# BSPD_SDC.net
KiCad netlist of a schematic drawn in Altium Designer
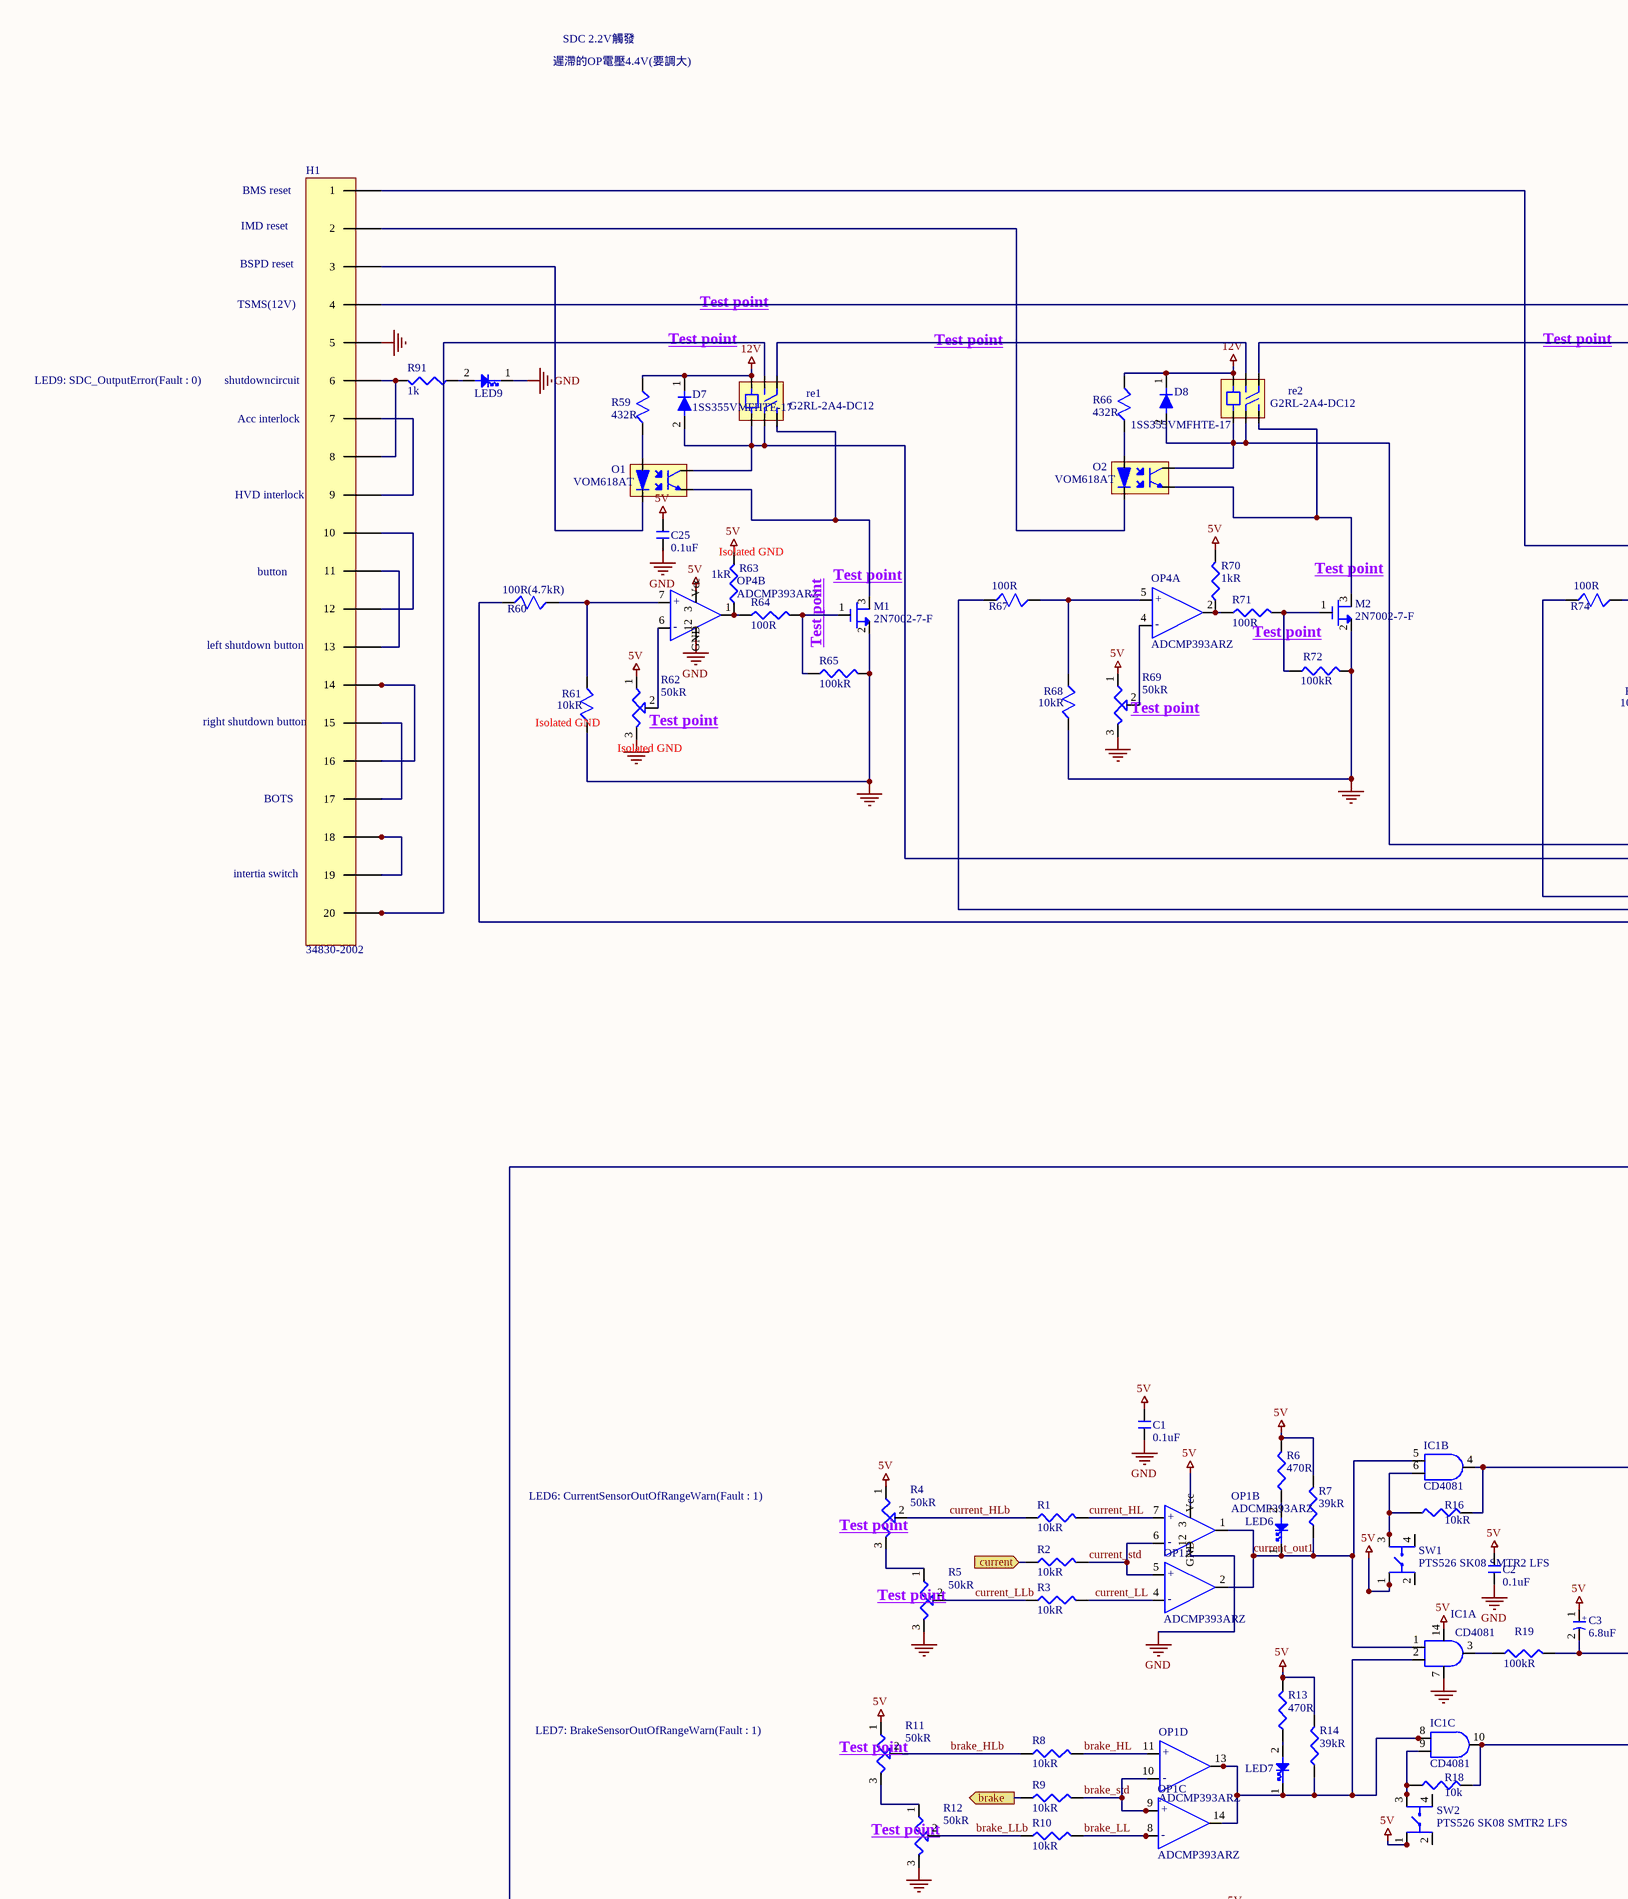
[diagram p0: BSPD+SDC.SchDoc, top left]
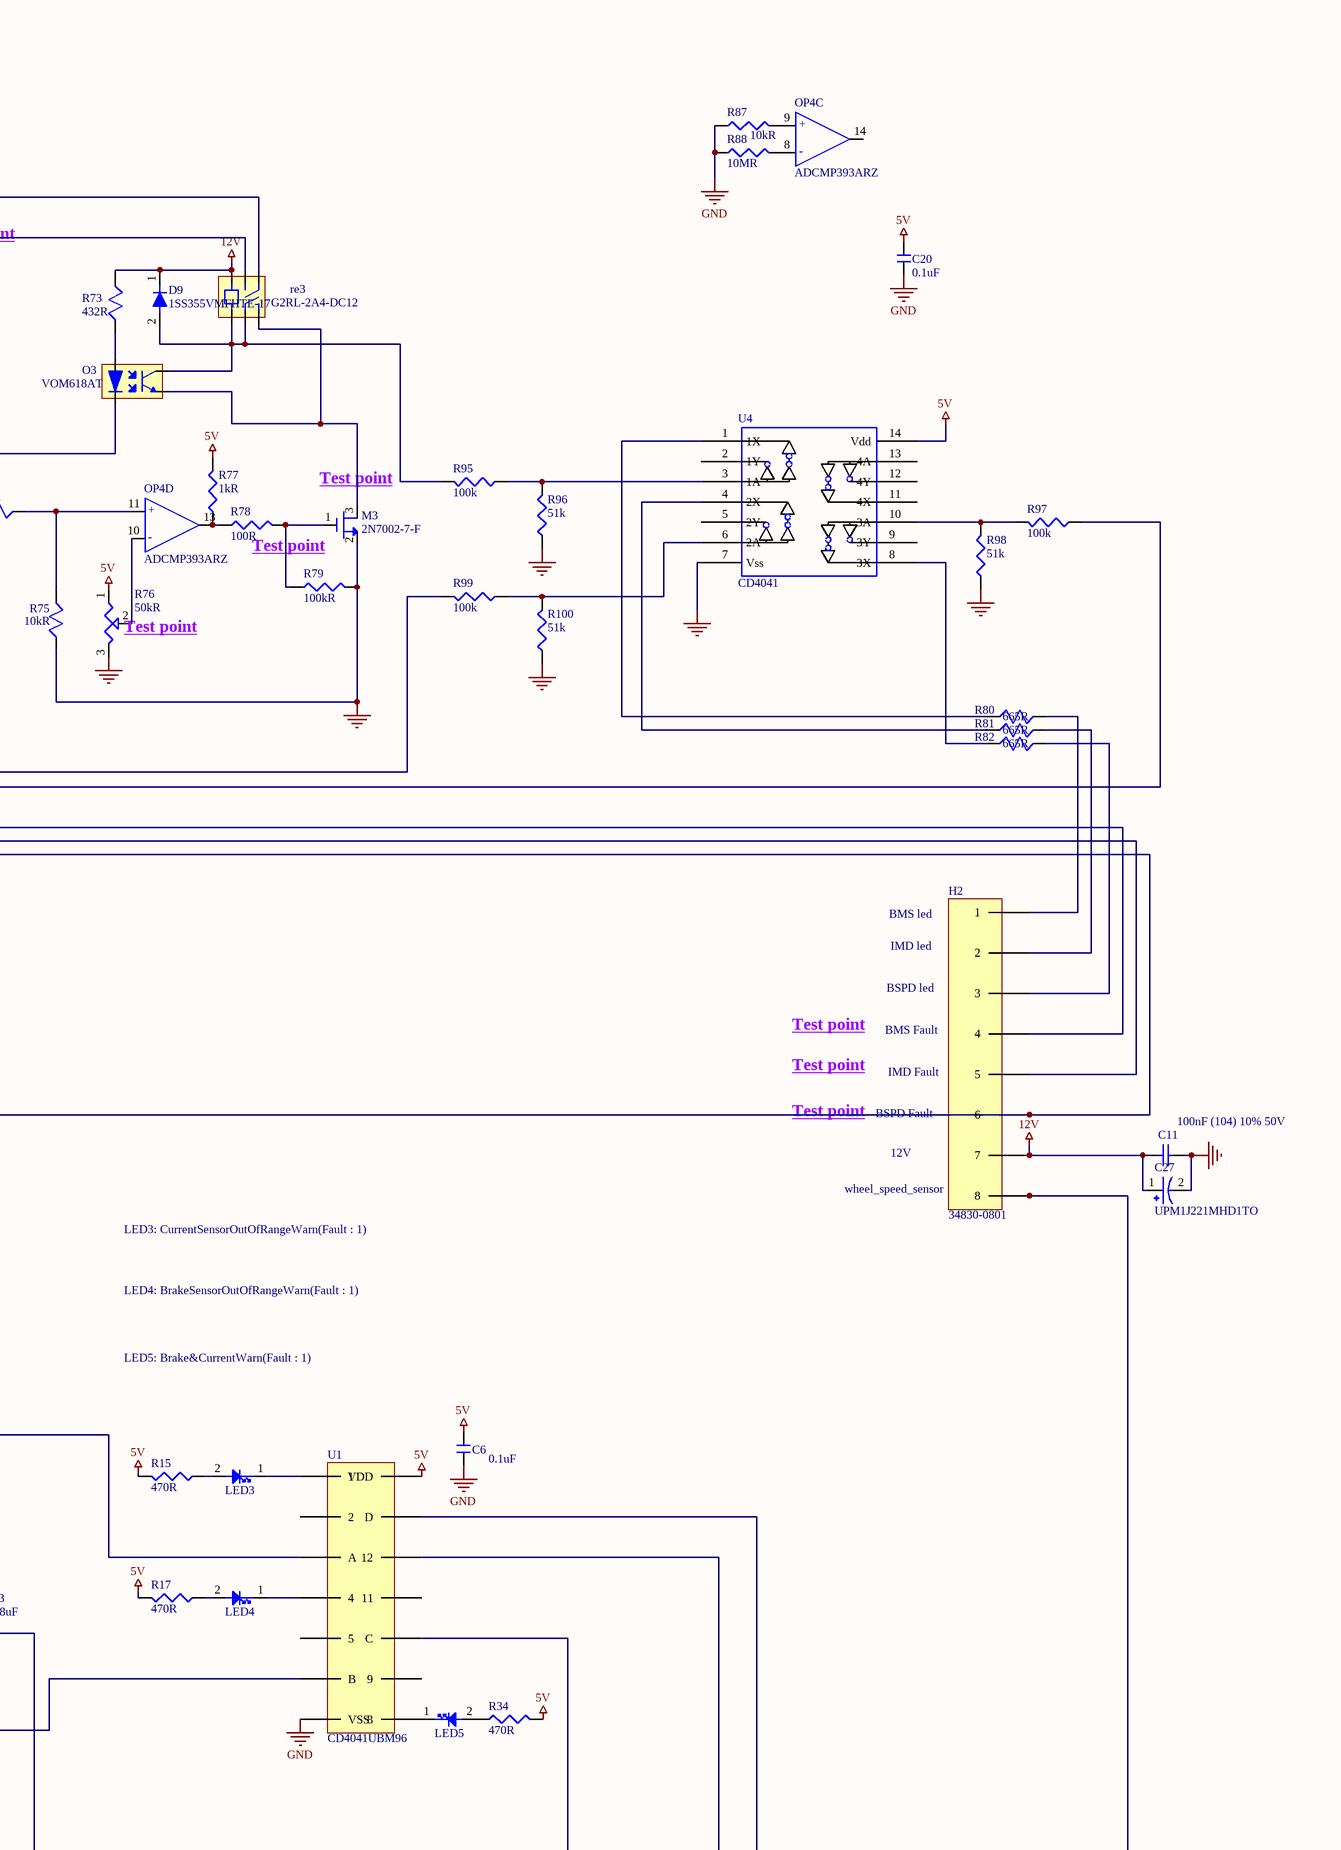
[diagram p1: BSPD+SDC.SchDoc, top right]
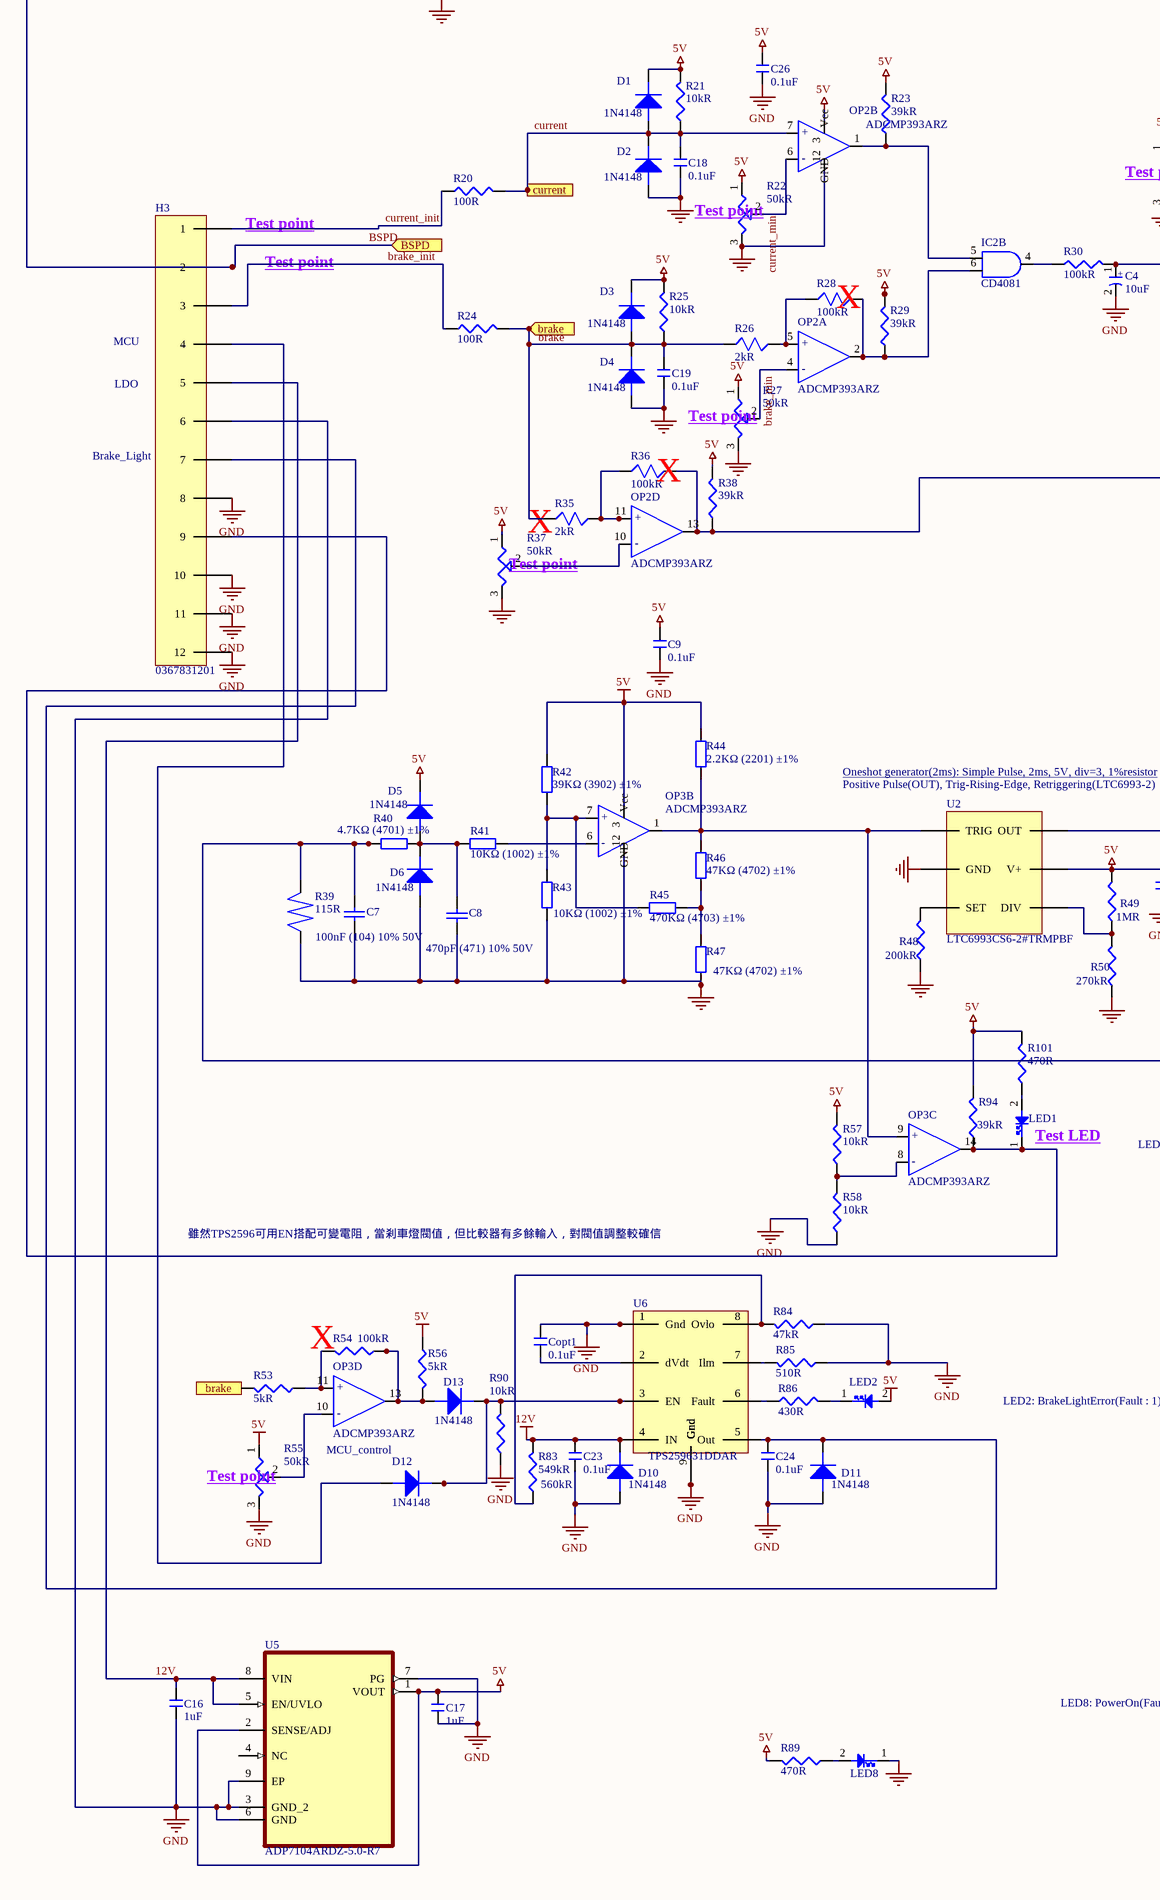
[diagram p2: BSPD+SDC.SchDoc, bottom left]
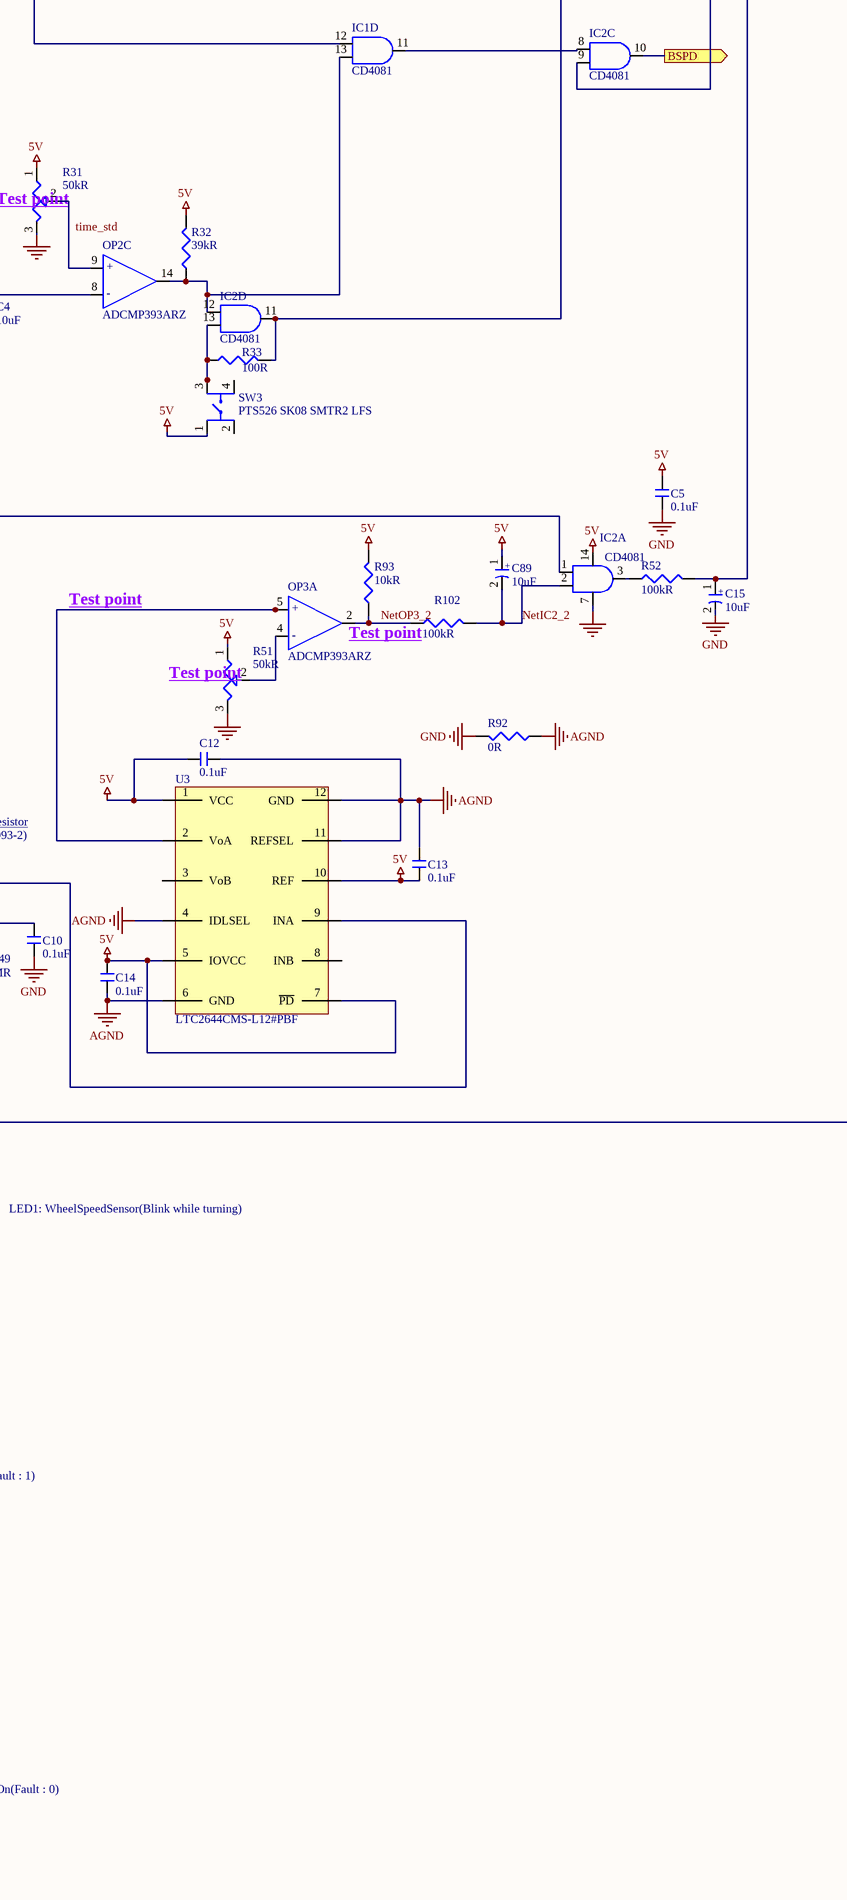
[diagram p3: BSPD+SDC.SchDoc, bottom right]

(export (version "E")
  (design (tool "Eeschema 10.0.6"))
  (components
    (comp (ref "C1")
      (value "0.1uF")
      (footprint "0805-0.1uF-Capacitor")
      (description "Cap Ceramic 0.1uF 50V X7R 10% Pad SMD 0603 Flexible Termination 125C Automotive")
      (fields
        (field (name "MANUFACTURER") "KEMET")
        (field (name "MANUFACTURER PART NUMBER") "C0603X104K5RAC3316")
      )
      (libsource (lib "BSPD_Schlib") (part "0.1uF-C0805C104M5RACTU"))
    )
    (comp (ref "C2")
      (value "0.1uF")
      (footprint "0805-0.1uF-Capacitor")
      (description "Cap Ceramic 0.1uF 50V X7R 10% Pad SMD 0603 Flexible Termination 125C Automotive")
      (fields
        (field (name "MANUFACTURER") "KEMET")
        (field (name "MANUFACTURER PART NUMBER") "C0603X104K5RAC3316")
      )
      (libsource (lib "BSPD_Schlib") (part "0.1uF-C0805C104M5RACTU"))
    )
    (comp (ref "C3")
      (value "6.8uF")
      (footprint "2312-6.8uF-Capacitor")
      (description "Cap Tant Solid 6.8uF 50V C CASE 10% (6 X 3.2 X 2.6mm) Inward L SMD 6032-28 1 Ohm 125C T/R")
      (fields (field (name "MANUFACTURER") "AVX") (field (name "MANUFACTURER PART NUMBER") "TAJC685K050RNJ"))
      (libsource (lib "BSPD_Schlib") (part "6.8uF-TAJC685K050RNJ"))
    )
    (comp (ref "C4")
      (value "10uF")
      (footprint "2312-6.8uF-Capacitor")
      (description "Cap Tant Solid 6.8uF 50V C CASE 10% (6 X 3.2 X 2.6mm) Inward L SMD 6032-28 1 Ohm 125C T/R")
      (fields (field (name "MANUFACTURER") "AVX") (field (name "MANUFACTURER PART NUMBER") "TAJC685K050RNJ"))
      (libsource (lib "BSPD_Schlib") (part "6.8uF-TAJC685K050RNJ"))
    )
    (comp (ref "C5")
      (value "0.1uF")
      (footprint "0805-0.1uF-Capacitor")
      (description "Cap Ceramic 0.1uF 50V X7R 10% Pad SMD 0603 Flexible Termination 125C Automotive")
      (fields
        (field (name "MANUFACTURER") "KEMET")
        (field (name "MANUFACTURER PART NUMBER") "C0603X104K5RAC3316")
      )
      (libsource (lib "BSPD_Schlib") (part "0.1uF-C0805C104M5RACTU"))
    )
    (comp (ref "C6")
      (value "0.1uF")
      (footprint "0805-0.1uF-Capacitor")
      (description "Cap Ceramic 0.1uF 50V X7R 10% Pad SMD 0603 Flexible Termination 125C Automotive")
      (fields
        (field (name "MANUFACTURER") "KEMET")
        (field (name "MANUFACTURER PART NUMBER") "C0603X104K5RAC3316")
      )
      (libsource (lib "BSPD_Schlib") (part "0.1uF-C0805C104M5RACTU"))
    )
    (comp (ref "C7")
      (value "100nF (104) 10% 50V")
      (footprint "1206_C")
      (description "贴片电容")
      (libsource (lib "wheelspeed") (part "1206 100nF (104) 10% 50V"))
    )
    (comp (ref "C8")
      (value "470pF (471) 10% 50V")
      (footprint "1206_C")
      (description "贴片电容")
      (libsource (lib "wheelspeed") (part "1206 470pF (471) 10% 50V"))
    )
    (comp (ref "C9")
      (value "0.1uF")
      (footprint "0805-0.1uF-Capacitor")
      (description "Cap Ceramic 0.1uF 50V X7R 10% Pad SMD 0603 Flexible Termination 125C Automotive")
      (fields
        (field (name "MANUFACTURER") "KEMET")
        (field (name "MANUFACTURER PART NUMBER") "C0603X104K5RAC3316")
      )
      (libsource (lib "BSPD_Schlib") (part "0.1uF-C0805C104M5RACTU"))
    )
    (comp (ref "C10")
      (value "0.1uF")
      (footprint "0805-0.1uF-Capacitor")
      (description "Cap Ceramic 0.1uF 50V X7R 10% Pad SMD 0603 Flexible Termination 125C Automotive")
      (fields
        (field (name "MANUFACTURER") "KEMET")
        (field (name "MANUFACTURER PART NUMBER") "C0603X104K5RAC3316")
      )
      (libsource (lib "BSPD_Schlib") (part "0.1uF-C0805C104M5RACTU"))
    )
    (comp (ref "C11")
      (value "100nF (104) 10% 50V")
      (footprint "1206_C")
      (description "贴片电容")
      (libsource (lib "wheelspeed") (part "1206 100nF (104) 10% 50V"))
    )
    (comp (ref "C12")
      (value "0.1uF")
      (footprint "0805-0.1uF-Capacitor")
      (description "Cap Ceramic 0.1uF 50V X7R 10% Pad SMD 0603 Flexible Termination 125C Automotive")
      (fields
        (field (name "MANUFACTURER") "KEMET")
        (field (name "MANUFACTURER PART NUMBER") "C0603X104K5RAC3316")
      )
      (libsource (lib "BSPD_Schlib") (part "0.1uF-C0805C104M5RACTU"))
    )
    (comp (ref "C13")
      (value "0.1uF")
      (footprint "0805-0.1uF-Capacitor")
      (description "Cap Ceramic 0.1uF 50V X7R 10% Pad SMD 0603 Flexible Termination 125C Automotive")
      (fields
        (field (name "MANUFACTURER") "KEMET")
        (field (name "MANUFACTURER PART NUMBER") "C0603X104K5RAC3316")
      )
      (libsource (lib "BSPD_Schlib") (part "0.1uF-C0805C104M5RACTU"))
    )
    (comp (ref "C14")
      (value "0.1uF")
      (footprint "0805-0.1uF-Capacitor")
      (description "Cap Ceramic 0.1uF 50V X7R 10% Pad SMD 0603 Flexible Termination 125C Automotive")
      (fields
        (field (name "MANUFACTURER") "KEMET")
        (field (name "MANUFACTURER PART NUMBER") "C0603X104K5RAC3316")
      )
      (libsource (lib "BSPD_Schlib") (part "0.1uF-C0805C104M5RACTU"))
    )
    (comp (ref "C15")
      (value "10uF")
      (footprint "2312-6.8uF-Capacitor")
      (description "Cap Tant Solid 6.8uF 50V C CASE 10% (6 X 3.2 X 2.6mm) Inward L SMD 6032-28 1 Ohm 125C T/R")
      (fields (field (name "MANUFACTURER") "AVX") (field (name "MANUFACTURER PART NUMBER") "TAJC685K050RNJ"))
      (libsource (lib "BSPD_Schlib") (part "6.8uF-TAJC685K050RNJ"))
    )
    (comp (ref "C16")
      (value "1uF")
      (footprint "0805-0.47uF-CAPACITOR")
      (description "Cap Cer 0805 1uF 25V X7R 10%")
      (fields
        (field (name "MANUFACTURER") "KEMET")
        (field (name "MANUFACTURER PART NUMBER") "C0805C474K3REC7210")
      )
      (libsource (lib "BSPD_Schlib") (part "1uF-0805DC105KAT2A"))
    )
    (comp (ref "C17")
      (value "1uF")
      (footprint "0805-0.47uF-CAPACITOR")
      (description "Cap Cer 0805 470NF 25V X7R 10%")
      (fields
        (field (name "MANUFACTURER") "KEMET")
        (field (name "MANUFACTURER PART NUMBER") "C0805C474K3REC7210")
      )
      (libsource (lib "BSPD_Schlib") (part "0.47uF-C0805C474K3REC7210"))
    )
    (comp (ref "C18")
      (value "0.1uF")
      (footprint "0805-0.1uF-Capacitor")
      (description "Cap Ceramic 0.1uF 50V X7R 10% Pad SMD 0603 Flexible Termination 125C Automotive")
      (fields
        (field (name "MANUFACTURER") "KEMET")
        (field (name "MANUFACTURER PART NUMBER") "C0603X104K5RAC3316")
      )
      (libsource (lib "BSPD_Schlib") (part "0.1uF-C0805C104M5RACTU"))
    )
    (comp (ref "C19")
      (value "0.1uF")
      (footprint "0805-0.1uF-Capacitor")
      (description "Cap Ceramic 0.1uF 50V X7R 10% Pad SMD 0603 Flexible Termination 125C Automotive")
      (fields
        (field (name "MANUFACTURER") "KEMET")
        (field (name "MANUFACTURER PART NUMBER") "C0603X104K5RAC3316")
      )
      (libsource (lib "BSPD_Schlib") (part "0.1uF-C0805C104M5RACTU"))
    )
    (comp (ref "C20")
      (value "0.1uF")
      (footprint "0805-0.1uF-Capacitor")
      (description "Cap Ceramic 0.1uF 50V X7R 10% Pad SMD 0603 Flexible Termination 125C Automotive")
      (fields
        (field (name "MANUFACTURER") "KEMET")
        (field (name "MANUFACTURER PART NUMBER") "C0603X104K5RAC3316")
      )
      (libsource (lib "BSPD_Schlib") (part "0.1uF-C0805C104M5RACTU"))
    )
    (comp (ref "C23")
      (value "0.1uF")
      (footprint "0805-0.1uF-Capacitor")
      (description "Cap Ceramic 0.1uF 50V X7R 10% Pad SMD 0603 Flexible Termination 125C Automotive")
      (fields
        (field (name "MANUFACTURER") "KEMET")
        (field (name "MANUFACTURER PART NUMBER") "C0603X104K5RAC3316")
      )
      (libsource (lib "BSPD_Schlib") (part "0.1uF-C0805C104M5RACTU"))
    )
    (comp (ref "C24")
      (value "0.1uF")
      (footprint "0805-0.1uF-Capacitor")
      (description "Cap Ceramic 0.1uF 50V X7R 10% Pad SMD 0603 Flexible Termination 125C Automotive")
      (fields
        (field (name "MANUFACTURER") "KEMET")
        (field (name "MANUFACTURER PART NUMBER") "C0603X104K5RAC3316")
      )
      (libsource (lib "BSPD_Schlib") (part "0.1uF-C0805C104M5RACTU"))
    )
    (comp (ref "C25")
      (value "0.1uF")
      (footprint "0805-0.1uF-Capacitor")
      (description "Cap Ceramic 0.1uF 50V X7R 10% Pad SMD 0603 Flexible Termination 125C Automotive")
      (fields
        (field (name "MANUFACTURER") "KEMET")
        (field (name "MANUFACTURER PART NUMBER") "C0603X104K5RAC3316")
      )
      (libsource (lib "BSPD_Schlib") (part "0.1uF-C0805C104M5RACTU"))
    )
    (comp (ref "C26")
      (value "0.1uF")
      (footprint "0805-0.1uF-Capacitor")
      (description "Cap Ceramic 0.1uF 50V X7R 10% Pad SMD 0603 Flexible Termination 125C Automotive")
      (fields
        (field (name "MANUFACTURER") "KEMET")
        (field (name "MANUFACTURER PART NUMBER") "C0603X104K5RAC3316")
      )
      (libsource (lib "BSPD_Schlib") (part "0.1uF-C0805C104M5RACTU"))
    )
    (comp (ref "C27")
      (value "UPM1J221MHD1TO")
      (footprint "CAPPRD500W60D1250H2200")
      (description "Cap Aluminum 220uF 63V 20% (12.5 X 20mm) Radial 7.5mm 835mA 5000h 105°C Ammo Pack")
      (fields (field (name "MANUFACTURER") "Nichicon") (field (name "TOLERANCE") "20%"))
      (libsource (lib "BSPD_Schlib") (part "UPM1J221MHD1TO"))
    )
    (comp (ref "C89")
      (value "10uF")
      (footprint "2312-6.8uF-Capacitor")
      (description "Cap Tant Solid 6.8uF 50V C CASE 10% (6 X 3.2 X 2.6mm) Inward L SMD 6032-28 1 Ohm 125C T/R")
      (fields (field (name "MANUFACTURER") "AVX") (field (name "MANUFACTURER PART NUMBER") "TAJC685K050RNJ"))
      (libsource (lib "BSPD_Schlib") (part "6.8uF-TAJC685K050RNJ"))
    )
    (comp (ref "Copt1")
      (value "0.1uF")
      (footprint "0805-0.1uF-Capacitor")
      (description "Cap Ceramic 0.1uF 50V X7R 10% Pad SMD 0603 Flexible Termination 125C Automotive")
      (fields
        (field (name "MANUFACTURER") "KEMET")
        (field (name "MANUFACTURER PART NUMBER") "C0603X104K5RAC3316")
      )
      (libsource (lib "BSPD_Schlib") (part "0.1uF-C0805C104M5RACTU"))
    )
    (comp (ref "D1")
      (value "1N4148")
      (footprint "1N4148W-TP")
      (description "1N4148W Series 100 V 150 mA 4 ns SMT High Speed Switching Diode - SOD-123")
      (fields (field (name "MANUFACTURER") "MCC") (field (name "MANUFACTURER PART NUMBER") "1N4148W-TP"))
      (libsource (lib "BSPD_Schlib") (part "1N4148W-TP"))
    )
    (comp (ref "D2")
      (value "1N4148")
      (footprint "1N4148W-TP")
      (description "1N4148W Series 100 V 150 mA 4 ns SMT High Speed Switching Diode - SOD-123")
      (fields (field (name "MANUFACTURER") "MCC") (field (name "MANUFACTURER PART NUMBER") "1N4148W-TP"))
      (libsource (lib "BSPD_Schlib") (part "1N4148W-TP"))
    )
    (comp (ref "D3")
      (value "1N4148")
      (footprint "1N4148W-TP")
      (description "1N4148W Series 100 V 150 mA 4 ns SMT High Speed Switching Diode - SOD-123")
      (fields (field (name "MANUFACTURER") "MCC") (field (name "MANUFACTURER PART NUMBER") "1N4148W-TP"))
      (libsource (lib "BSPD_Schlib") (part "1N4148W-TP"))
    )
    (comp (ref "D4")
      (value "1N4148")
      (footprint "1N4148W-TP")
      (description "1N4148W Series 100 V 150 mA 4 ns SMT High Speed Switching Diode - SOD-123")
      (fields (field (name "MANUFACTURER") "MCC") (field (name "MANUFACTURER PART NUMBER") "1N4148W-TP"))
      (libsource (lib "BSPD_Schlib") (part "1N4148W-TP"))
    )
    (comp (ref "D5")
      (value "1N4148")
      (footprint "1N4148W-TP")
      (description "1N4148W Series 100 V 150 mA 4 ns SMT High Speed Switching Diode - SOD-123")
      (fields (field (name "MANUFACTURER") "MCC") (field (name "MANUFACTURER PART NUMBER") "1N4148W-TP"))
      (libsource (lib "BSPD_Schlib") (part "1N4148W-TP"))
    )
    (comp (ref "D6")
      (value "1N4148")
      (footprint "1N4148W-TP")
      (description "1N4148W Series 100 V 150 mA 4 ns SMT High Speed Switching Diode - SOD-123")
      (fields (field (name "MANUFACTURER") "MCC") (field (name "MANUFACTURER PART NUMBER") "1N4148W-TP"))
      (libsource (lib "BSPD_Schlib") (part "1N4148W-TP"))
    )
    (comp (ref "D7")
      (value "1SS355VMFHTE-17")
      (footprint "1SS355VMFHTE-17")
      (fields (field (name "MANUFACTURER") "Rohm"))
      (libsource (lib "shutdown_circuit") (part "1SS355VMFHTE-17"))
    )
    (comp (ref "D8")
      (value "1SS355VMFHTE-17")
      (footprint "1SS355VMFHTE-17")
      (fields (field (name "MANUFACTURER") "Rohm"))
      (libsource (lib "shutdown_circuit") (part "1SS355VMFHTE-17"))
    )
    (comp (ref "D9")
      (value "1SS355VMFHTE-17")
      (footprint "1SS355VMFHTE-17")
      (fields (field (name "MANUFACTURER") "Rohm"))
      (libsource (lib "shutdown_circuit") (part "1SS355VMFHTE-17"))
    )
    (comp (ref "D10")
      (value "1N4148")
      (footprint "1N4148W-TP")
      (description "1N4148W Series 100 V 150 mA 4 ns SMT High Speed Switching Diode - SOD-123")
      (fields (field (name "MANUFACTURER") "MCC") (field (name "MANUFACTURER PART NUMBER") "1N4148W-TP"))
      (libsource (lib "BSPD_Schlib") (part "1N4148W-TP"))
    )
    (comp (ref "D11")
      (value "1N4148")
      (footprint "1N4148W-TP")
      (description "1N4148W Series 100 V 150 mA 4 ns SMT High Speed Switching Diode - SOD-123")
      (fields (field (name "MANUFACTURER") "MCC") (field (name "MANUFACTURER PART NUMBER") "1N4148W-TP"))
      (libsource (lib "BSPD_Schlib") (part "1N4148W-TP"))
    )
    (comp (ref "D12")
      (value "1N4148")
      (footprint "1N4148W-TP")
      (description "1N4148W Series 100 V 150 mA 4 ns SMT High Speed Switching Diode - SOD-123")
      (fields (field (name "MANUFACTURER") "MCC") (field (name "MANUFACTURER PART NUMBER") "1N4148W-TP"))
      (libsource (lib "BSPD_Schlib") (part "1N4148W-TP"))
    )
    (comp (ref "D13")
      (value "1N4148")
      (footprint "1N4148W-TP")
      (description "1N4148W Series 100 V 150 mA 4 ns SMT High Speed Switching Diode - SOD-123")
      (fields (field (name "MANUFACTURER") "MCC") (field (name "MANUFACTURER PART NUMBER") "1N4148W-TP"))
      (libsource (lib "BSPD_Schlib") (part "1N4148W-TP"))
    )
    (comp (ref "H1")
      (value "34830-2002")
      (footprint "348302002")
      (description "MX150 2x10 Dual Row Right-Angle Header, 20 Circuits, Keying Option B, Light Gray, Solder Tail")
      (fields (field (name "MANUFACTURER") "Molex"))
      (libsource (lib "BSPD_Schlib") (part "34830-2002"))
    )
    (comp (ref "H2")
      (value "34830-0801")
      (footprint "MOLEX_34830-0801")
      (description "MX150 2x4 Dual Row Right-Angle Header, 8 Circuits, Keying Option A, Black, Solder Tail")
      (fields (field (name "MANUFACTURER") "Molex"))
      (libsource (lib "BSPD_Schlib") (part "34830-0801"))
    )
    (comp (ref "H3")
      (value "0367831201")
      (footprint "MOLEX_36783-1201")
      (description "MX120G Sealed Header Connector Assembly, 12 Circuit, Color Mark Identification Black")
      (fields (field (name "MANUFACTURER") "Molex"))
      (libsource (lib "BSPD_Schlib") (part "0367831201"))
    )
    (comp (ref "IC1")
      (value "CD4081")
      (footprint "CD4081BM")
      (description "In a Tube of 50, Texas Instruments CD4081BM, Quad 2-Input AND Logic Gate, 14-Pin SOIC")
      (fields
        (field (name "MANUFACTURER") "Texas Instruments")
        (field (name "MANUFACTURER PART NUMBER") "CD4081BM")
      )
      (libsource (lib "BSPD_Schlib") (part "CD4081BM"))
    )
    (comp (ref "IC2")
      (value "CD4081")
      (footprint "CD4081BM")
      (description "In a Tube of 50, Texas Instruments CD4081BM, Quad 2-Input AND Logic Gate, 14-Pin SOIC")
      (fields
        (field (name "MANUFACTURER") "Texas Instruments")
        (field (name "MANUFACTURER PART NUMBER") "CD4081BM")
      )
      (libsource (lib "BSPD_Schlib") (part "CD4081BM"))
    )
    (comp (ref "LED1")
      (value "led-150080RS75000")
      (footprint "led-0805")
      (description "On a Reel of 4000, 2 V Red LED 2012 (0805) SMD, Wurth Elektronik WL-SMCW 150080RS75000")
      (fields
        (field (name "MANUFACTURER") "Würth Elektronik")
        (field (name "MANUFACTURER PART NUMBER") "150080RS75000")
      )
      (libsource (lib "altium-import") (part "root_1_led-150080RS75000_"))
    )
    (comp (ref "LED2")
      (value "led-150080RS75000")
      (footprint "led-0805")
      (description "On a Reel of 4000, 2 V Red LED 2012 (0805) SMD, Wurth Elektronik WL-SMCW 150080RS75000")
      (fields
        (field (name "MANUFACTURER") "Würth Elektronik")
        (field (name "MANUFACTURER PART NUMBER") "150080RS75000")
      )
      (libsource (lib "altium-import") (part "root_0_led-150080RS75000_"))
    )
    (comp (ref "LED3")
      (value "led-150080RS75000")
      (footprint "led-0805")
      (description "On a Reel of 4000, 2 V Red LED 2012 (0805) SMD, Wurth Elektronik WL-SMCW 150080RS75000")
      (fields
        (field (name "MANUFACTURER") "Würth Elektronik")
        (field (name "MANUFACTURER PART NUMBER") "150080RS75000")
      )
      (libsource (lib "altium-import") (part "root_2_led-150080RS75000_"))
    )
    (comp (ref "LED4")
      (value "led-150080RS75000")
      (footprint "led-0805")
      (description "On a Reel of 4000, 2 V Red LED 2012 (0805) SMD, Wurth Elektronik WL-SMCW 150080RS75000")
      (fields
        (field (name "MANUFACTURER") "Würth Elektronik")
        (field (name "MANUFACTURER PART NUMBER") "150080RS75000")
      )
      (libsource (lib "altium-import") (part "root_2_led-150080RS75000_"))
    )
    (comp (ref "LED5")
      (value "led-150080RS75000")
      (footprint "led-0805")
      (description "On a Reel of 4000, 2 V Red LED 2012 (0805) SMD, Wurth Elektronik WL-SMCW 150080RS75000")
      (fields
        (field (name "MANUFACTURER") "Würth Elektronik")
        (field (name "MANUFACTURER PART NUMBER") "150080RS75000")
      )
      (libsource (lib "altium-import") (part "root_0_led-150080RS75000_"))
    )
    (comp (ref "LED6")
      (value "led-150080RS75000")
      (footprint "led-0805")
      (description "On a Reel of 4000, 2 V Red LED 2012 (0805) SMD, Wurth Elektronik WL-SMCW 150080RS75000")
      (fields
        (field (name "MANUFACTURER") "Würth Elektronik")
        (field (name "MANUFACTURER PART NUMBER") "150080RS75000")
      )
      (libsource (lib "altium-import") (part "root_1_led-150080RS75000_"))
    )
    (comp (ref "LED7")
      (value "led-150080RS75000")
      (footprint "led-0805")
      (description "On a Reel of 4000, 2 V Red LED 2012 (0805) SMD, Wurth Elektronik WL-SMCW 150080RS75000")
      (fields
        (field (name "MANUFACTURER") "Würth Elektronik")
        (field (name "MANUFACTURER PART NUMBER") "150080RS75000")
      )
      (libsource (lib "altium-import") (part "root_1_led-150080RS75000_"))
    )
    (comp (ref "LED8")
      (value "led-150080RS75000")
      (footprint "led-0805")
      (description "On a Reel of 4000, 2 V Red LED 2012 (0805) SMD, Wurth Elektronik WL-SMCW 150080RS75000")
      (fields
        (field (name "MANUFACTURER") "Würth Elektronik")
        (field (name "MANUFACTURER PART NUMBER") "150080RS75000")
      )
      (libsource (lib "altium-import") (part "root_2_led-150080RS75000_"))
    )
    (comp (ref "LED9")
      (value "led-150080RS75000")
      (footprint "led-0805")
      (description "On a Reel of 4000, 2 V Red LED 2012 (0805) SMD, Wurth Elektronik WL-SMCW 150080RS75000")
      (fields
        (field (name "MANUFACTURER") "Würth Elektronik")
        (field (name "MANUFACTURER PART NUMBER") "150080RS75000")
      )
      (libsource (lib "altium-import") (part "root_2_led-150080RS75000_"))
    )
    (comp (ref "M1")
      (value "2N7002-7-F")
      (footprint "2N7002-7-F")
      (fields (field (name "MANUFACTURER") "Diodes Inc.") (field (name "VOLTAGE") "60V"))
      (libsource (lib "shutdown_circuit") (part "2N7002-7-F"))
    )
    (comp (ref "M2")
      (value "2N7002-7-F")
      (footprint "2N7002-7-F")
      (fields (field (name "MANUFACTURER") "Diodes Inc.") (field (name "VOLTAGE") "60V"))
      (libsource (lib "shutdown_circuit") (part "2N7002-7-F"))
    )
    (comp (ref "M3")
      (value "2N7002-7-F")
      (footprint "2N7002-7-F")
      (fields (field (name "MANUFACTURER") "Diodes Inc.") (field (name "VOLTAGE") "60V"))
      (libsource (lib "shutdown_circuit") (part "2N7002-7-F"))
    )
    (comp (ref "O1")
      (value "VOM618AT")
      (footprint "VOM618AT")
      (description "VOM618AT DC Input Phototransistor Output Optocoupler, Surface Mount, 4-Pin SOP")
      (fields (field (name "MANUFACTURER") "Vishay"))
      (libsource (lib "shutdown_circuit") (part "VOM618AT"))
    )
    (comp (ref "O2")
      (value "VOM618AT")
      (footprint "VOM618AT")
      (description "VOM618AT DC Input Phototransistor Output Optocoupler, Surface Mount, 4-Pin SOP")
      (fields (field (name "MANUFACTURER") "Vishay"))
      (libsource (lib "shutdown_circuit") (part "VOM618AT"))
    )
    (comp (ref "O3")
      (value "VOM618AT")
      (footprint "VOM618AT")
      (description "VOM618AT DC Input Phototransistor Output Optocoupler, Surface Mount, 4-Pin SOP")
      (fields (field (name "MANUFACTURER") "Vishay"))
      (libsource (lib "shutdown_circuit") (part "VOM618AT"))
    )
    (comp (ref "OP1")
      (value "ADCMP393ARZ")
      (footprint "ADCMP393ARZ:SOIC127P600X175-14N")
      (description "Comparator Quad R-R I/P 5.5V 14-Pin TSSOP Tube")
      (fields
        (field (name "MANUFACTURER") "Analog Devices")
        (field (name "MANUFACTURER PART NUMBER") "ADCMP393ARUZ")
      )
      (libsource (lib "BSPD_Schlib") (part "ADCMP393ARZ"))
    )
    (comp (ref "OP2")
      (value "ADCMP393ARZ")
      (footprint "ADCMP393ARZ:SOIC127P600X175-14N")
      (description "Comparator Quad R-R I/P 5.5V 14-Pin TSSOP Tube")
      (fields
        (field (name "MANUFACTURER") "Analog Devices")
        (field (name "MANUFACTURER PART NUMBER") "ADCMP393ARUZ")
      )
      (libsource (lib "BSPD_Schlib") (part "ADCMP393ARZ"))
    )
    (comp (ref "OP3")
      (value "ADCMP393ARZ")
      (footprint "ADCMP393ARZ:SOIC127P600X175-14N")
      (description "Comparator Quad R-R I/P 5.5V 14-Pin TSSOP Tube")
      (fields
        (field (name "MANUFACTURER") "Analog Devices")
        (field (name "MANUFACTURER PART NUMBER") "ADCMP393ARUZ")
      )
      (libsource (lib "BSPD_Schlib") (part "ADCMP393ARZ"))
    )
    (comp (ref "OP4")
      (value "ADCMP393ARZ")
      (footprint "ADCMP393ARZ:SOIC127P600X175-14N")
      (description "Comparator Quad R-R I/P 5.5V 14-Pin TSSOP Tube")
      (fields
        (field (name "MANUFACTURER") "Analog Devices")
        (field (name "MANUFACTURER PART NUMBER") "ADCMP393ARUZ")
      )
      (libsource (lib "BSPD_Schlib") (part "ADCMP393ARZ"))
    )
    (comp (ref "R1")
      (value "10kR")
      (footprint "0805-Resistor")
      (description "Res Thick Film 0805 10K Ohm 1% 1/8W ±100ppm/°C Molded SMD Paper T/R")
      (fields
        (field (name "MANUFACTURER") "Vishay")
        (field (name "MANUFACTURER PART NUMBER") "CRCW080510K0FKEAC")
      )
      (libsource (lib "BSPD_Schlib") (part "10k-CRCW080510K0FKEAC"))
    )
    (comp (ref "R2")
      (value "10kR")
      (footprint "0805-Resistor")
      (description "Res Thick Film 0805 10K Ohm 1% 1/8W ±100ppm/°C Molded SMD Paper T/R")
      (fields
        (field (name "MANUFACTURER") "Vishay")
        (field (name "MANUFACTURER PART NUMBER") "CRCW080510K0FKEAC")
      )
      (libsource (lib "BSPD_Schlib") (part "10k-CRCW080510K0FKEAC"))
    )
    (comp (ref "R3")
      (value "10kR")
      (footprint "0805-Resistor")
      (description "Res Thick Film 0805 10K Ohm 1% 1/8W ±100ppm/°C Molded SMD Paper T/R")
      (fields
        (field (name "MANUFACTURER") "Vishay")
        (field (name "MANUFACTURER PART NUMBER") "CRCW080510K0FKEAC")
      )
      (libsource (lib "BSPD_Schlib") (part "10k-CRCW080510K0FKEAC"))
    )
    (comp (ref "R4")
      (value "50kR")
      (footprint "50kR-vertical")
      (description "Trimmer; Cermet; Rest 50 Kilohms; PCB; Pwr-Rtg 0.5W; Dim 0.375InLx0.19InWx0.395InH")
      (fields
        (field (name "MANUFACTURER") "Bourns")
        (field (name "MANUFACTURER PART NUMBER") "3296W-1-503LF")
      )
      (libsource (lib "BSPD_Schlib") (part "50K可變垂直-3296W-1-503LF"))
    )
    (comp (ref "R5")
      (value "50kR")
      (footprint "50kR-vertical")
      (description "Trimmer; Cermet; Rest 50 Kilohms; PCB; Pwr-Rtg 0.5W; Dim 0.375InLx0.19InWx0.395InH")
      (fields
        (field (name "MANUFACTURER") "Bourns")
        (field (name "MANUFACTURER PART NUMBER") "3296W-1-503LF")
      )
      (libsource (lib "BSPD_Schlib") (part "50K可變垂直-3296W-1-503LF"))
    )
    (comp (ref "R6")
      (value "470R")
      (footprint "0805-Resistor")
      (description "Res Thick Film 0805 470 Ohm 1% 1/8W ±100ppm/°C Molded SMD Paper T/R")
      (fields
        (field (name "MANUFACTURER") "Vishay")
        (field (name "MANUFACTURER PART NUMBER") "CRCW0805470RFKEAC")
      )
      (libsource (lib "BSPD_Schlib") (part "470-CRCW0805470RFKEAC"))
    )
    (comp (ref "R7")
      (value "39kR")
      (footprint "0805-Resistor")
      (description "CRCW Thick Film Commodity Chip Resistor 0805 Size 39K Ohm 1% 0.125 W 100 ppm/K 2-Pin SMD Paper T/R")
      (fields
        (field (name "MANUFACTURER") "Vishay")
        (field (name "MANUFACTURER PART NUMBER") "CRCW080539K0FKEAC")
      )
      (libsource (lib "BSPD_Schlib") (part "39k-CRCW080539K0FKEAC"))
    )
    (comp (ref "R8")
      (value "10kR")
      (footprint "0805-Resistor")
      (description "Res Thick Film 0805 10K Ohm 1% 1/8W ±100ppm/°C Molded SMD Paper T/R")
      (fields
        (field (name "MANUFACTURER") "Vishay")
        (field (name "MANUFACTURER PART NUMBER") "CRCW080510K0FKEAC")
      )
      (libsource (lib "BSPD_Schlib") (part "10k-CRCW080510K0FKEAC"))
    )
    (comp (ref "R9")
      (value "10kR")
      (footprint "0805-Resistor")
      (description "Res Thick Film 0805 10K Ohm 1% 1/8W ±100ppm/°C Molded SMD Paper T/R")
      (fields
        (field (name "MANUFACTURER") "Vishay")
        (field (name "MANUFACTURER PART NUMBER") "CRCW080510K0FKEAC")
      )
      (libsource (lib "BSPD_Schlib") (part "10k-CRCW080510K0FKEAC"))
    )
    (comp (ref "R10")
      (value "10kR")
      (footprint "0805-Resistor")
      (description "Res Thick Film 0805 10K Ohm 1% 1/8W ±100ppm/°C Molded SMD Paper T/R")
      (fields
        (field (name "MANUFACTURER") "Vishay")
        (field (name "MANUFACTURER PART NUMBER") "CRCW080510K0FKEAC")
      )
      (libsource (lib "BSPD_Schlib") (part "10k-CRCW080510K0FKEAC"))
    )
    (comp (ref "R11")
      (value "50kR")
      (footprint "50kR-vertical")
      (description "Trimmer; Cermet; Rest 50 Kilohms; PCB; Pwr-Rtg 0.5W; Dim 0.375InLx0.19InWx0.395InH")
      (fields
        (field (name "MANUFACTURER") "Bourns")
        (field (name "MANUFACTURER PART NUMBER") "3296W-1-503LF")
      )
      (libsource (lib "BSPD_Schlib") (part "50K可變垂直-3296W-1-503LF"))
    )
    (comp (ref "R12")
      (value "50kR")
      (footprint "50kR-vertical")
      (description "Trimmer; Cermet; Rest 50 Kilohms; PCB; Pwr-Rtg 0.5W; Dim 0.375InLx0.19InWx0.395InH")
      (fields
        (field (name "MANUFACTURER") "Bourns")
        (field (name "MANUFACTURER PART NUMBER") "3296W-1-503LF")
      )
      (libsource (lib "BSPD_Schlib") (part "50K可變垂直-3296W-1-503LF"))
    )
    (comp (ref "R13")
      (value "470R")
      (footprint "0805-Resistor")
      (description "Res Thick Film 0805 470 Ohm 1% 1/8W ±100ppm/°C Molded SMD Paper T/R")
      (fields
        (field (name "MANUFACTURER") "Vishay")
        (field (name "MANUFACTURER PART NUMBER") "CRCW0805470RFKEAC")
      )
      (libsource (lib "BSPD_Schlib") (part "470-CRCW0805470RFKEAC"))
    )
    (comp (ref "R14")
      (value "39kR")
      (footprint "0805-Resistor")
      (description "CRCW Thick Film Commodity Chip Resistor 0805 Size 39K Ohm 1% 0.125 W 100 ppm/K 2-Pin SMD Paper T/R")
      (fields
        (field (name "MANUFACTURER") "Vishay")
        (field (name "MANUFACTURER PART NUMBER") "CRCW080539K0FKEAC")
      )
      (libsource (lib "BSPD_Schlib") (part "39k-CRCW080539K0FKEAC"))
    )
    (comp (ref "R15")
      (value "470R")
      (footprint "0805-Resistor")
      (description "Res Thick Film 0805 470 Ohm 1% 1/8W ±100ppm/°C Molded SMD Paper T/R")
      (fields
        (field (name "MANUFACTURER") "Vishay")
        (field (name "MANUFACTURER PART NUMBER") "CRCW0805470RFKEAC")
      )
      (libsource (lib "BSPD_Schlib") (part "470-CRCW0805470RFKEAC"))
    )
    (comp (ref "R16")
      (value "10kR")
      (footprint "0805-Resistor")
      (description "Res Thick Film 0805 100 Ohm 1% 1/8W ±100ppm/°C Molded SMD Paper T/R")
      (fields
        (field (name "MANUFACTURER") "Vishay")
        (field (name "MANUFACTURER PART NUMBER") "CRCW0805100RFKEAC")
      )
      (libsource (lib "altium-import") (part "root_0_100-CRCW0805100RFKEAC_"))
    )
    (comp (ref "R17")
      (value "470R")
      (footprint "0805-Resistor")
      (description "Res Thick Film 0805 470 Ohm 1% 1/8W ±100ppm/°C Molded SMD Paper T/R")
      (fields
        (field (name "MANUFACTURER") "Vishay")
        (field (name "MANUFACTURER PART NUMBER") "CRCW0805470RFKEAC")
      )
      (libsource (lib "BSPD_Schlib") (part "470-CRCW0805470RFKEAC"))
    )
    (comp (ref "R18")
      (value "10k")
      (footprint "0805-Resistor")
      (description "Res Thick Film 0805 100 Ohm 1% 1/8W ±100ppm/°C Molded SMD Paper T/R")
      (fields
        (field (name "MANUFACTURER") "Vishay")
        (field (name "MANUFACTURER PART NUMBER") "CRCW0805100RFKEAC")
      )
      (libsource (lib "altium-import") (part "root_0_100-CRCW0805100RFKEAC_"))
    )
    (comp (ref "R19")
      (value "100kR")
      (footprint "0805-Resistor")
      (description "Res Thick Film 0805 100K Ohm 1% 1/8W ±100ppm/°C Molded SMD Paper T/R")
      (fields
        (field (name "MANUFACTURER") "Vishay")
        (field (name "MANUFACTURER PART NUMBER") "CRCW0805100KFKEAC")
      )
      (libsource (lib "BSPD_Schlib") (part "100k-CRCW0805100KFKEAC"))
    )
    (comp (ref "R20")
      (value "100R")
      (footprint "0805-Resistor")
      (description "Res Thick Film 0805 100 Ohm 1% 1/8W ±100ppm/°C Molded SMD Paper T/R")
      (fields
        (field (name "MANUFACTURER") "Vishay")
        (field (name "MANUFACTURER PART NUMBER") "CRCW0805100RFKEAC")
      )
      (libsource (lib "BSPD_Schlib") (part "100-CRCW0805100RFKEAC"))
    )
    (comp (ref "R21")
      (value "10kR")
      (footprint "0805-Resistor")
      (description "CRCW Thick Film Commodity Chip Resistor 0805 Size 39K Ohm 1% 0.125 W 100 ppm/K 2-Pin SMD Paper T/R")
      (fields
        (field (name "MANUFACTURER") "Vishay")
        (field (name "MANUFACTURER PART NUMBER") "CRCW080539K0FKEAC")
      )
      (libsource (lib "BSPD_Schlib") (part "39k-CRCW080539K0FKEAC"))
    )
    (comp (ref "R22")
      (value "50kR")
      (footprint "50kR-vertical")
      (description "Trimmer; Cermet; Rest 50 Kilohms; PCB; Pwr-Rtg 0.5W; Dim 0.375InLx0.19InWx0.395InH")
      (fields
        (field (name "MANUFACTURER") "Bourns")
        (field (name "MANUFACTURER PART NUMBER") "3296W-1-503LF")
      )
      (libsource (lib "BSPD_Schlib") (part "50K可變垂直-3296W-1-503LF"))
    )
    (comp (ref "R23")
      (value "39kR")
      (footprint "0805-Resistor")
      (description "CRCW Thick Film Commodity Chip Resistor 0805 Size 39K Ohm 1% 0.125 W 100 ppm/K 2-Pin SMD Paper T/R")
      (fields
        (field (name "MANUFACTURER") "Vishay")
        (field (name "MANUFACTURER PART NUMBER") "CRCW080539K0FKEAC")
      )
      (libsource (lib "BSPD_Schlib") (part "39k-CRCW080539K0FKEAC"))
    )
    (comp (ref "R24")
      (value "100R")
      (footprint "0805-Resistor")
      (description "Res Thick Film 0805 100 Ohm 1% 1/8W ±100ppm/°C Molded SMD Paper T/R")
      (fields
        (field (name "MANUFACTURER") "Vishay")
        (field (name "MANUFACTURER PART NUMBER") "CRCW0805100RFKEAC")
      )
      (libsource (lib "BSPD_Schlib") (part "100-CRCW0805100RFKEAC"))
    )
    (comp (ref "R25")
      (value "10kR")
      (footprint "0805-Resistor")
      (description "CRCW Thick Film Commodity Chip Resistor 0805 Size 39K Ohm 1% 0.125 W 100 ppm/K 2-Pin SMD Paper T/R")
      (fields
        (field (name "MANUFACTURER") "Vishay")
        (field (name "MANUFACTURER PART NUMBER") "CRCW080539K0FKEAC")
      )
      (libsource (lib "BSPD_Schlib") (part "39k-CRCW080539K0FKEAC"))
    )
    (comp (ref "R26")
      (value "2kR")
      (footprint "2kR")
      (description "High Precision-High Stability Chip Resistor Thin Film 0805 2kOhm 1% Paper T/R")
      (fields
        (field (name "MANUFACTURER") "Yageo")
        (field (name "MANUFACTURER PART NUMBER") "RT0805FRE102KL")
      )
      (libsource (lib "shutdown_circuit") (part "RT0805FRE102KL"))
    )
    (comp (ref "R27")
      (value "50kR")
      (footprint "50kR-vertical")
      (description "Trimmer; Cermet; Rest 50 Kilohms; PCB; Pwr-Rtg 0.5W; Dim 0.375InLx0.19InWx0.395InH")
      (fields
        (field (name "MANUFACTURER") "Bourns")
        (field (name "MANUFACTURER PART NUMBER") "3296W-1-503LF")
      )
      (libsource (lib "BSPD_Schlib") (part "50K可變垂直-3296W-1-503LF"))
    )
    (comp (ref "R28")
      (value "100kR")
      (footprint "Yageo 0805")
      (description "Res Thin Film 0805 10K Ohm 1% 0.125W(1/8W) ±50ppm/C Molded SMD Paper T/R")
      (fields
        (field (name "MANUFACTURER") "Yageo")
        (field (name "MANUFACTURER PART NUMBER") "RT0805FRE1310KL")
      )
      (libsource (lib "shutdown_circuit") (part "RT0805FRE1310KL"))
    )
    (comp (ref "R29")
      (value "39kR")
      (footprint "0805-Resistor")
      (description "CRCW Thick Film Commodity Chip Resistor 0805 Size 39K Ohm 1% 0.125 W 100 ppm/K 2-Pin SMD Paper T/R")
      (fields
        (field (name "MANUFACTURER") "Vishay")
        (field (name "MANUFACTURER PART NUMBER") "CRCW080539K0FKEAC")
      )
      (libsource (lib "BSPD_Schlib") (part "39k-CRCW080539K0FKEAC"))
    )
    (comp (ref "R30")
      (value "100kR")
      (footprint "0805-Resistor")
      (description "Res Thick Film 0805 100K Ohm 1% 1/8W ±100ppm/°C Molded SMD Paper T/R")
      (fields
        (field (name "MANUFACTURER") "Vishay")
        (field (name "MANUFACTURER PART NUMBER") "CRCW0805100KFKEAC")
      )
      (libsource (lib "BSPD_Schlib") (part "100k-CRCW0805100KFKEAC"))
    )
    (comp (ref "R31")
      (value "50kR")
      (footprint "50kR-vertical")
      (description "Trimmer; Cermet; Rest 50 Kilohms; PCB; Pwr-Rtg 0.5W; Dim 0.375InLx0.19InWx0.395InH")
      (fields
        (field (name "MANUFACTURER") "Bourns")
        (field (name "MANUFACTURER PART NUMBER") "3296W-1-503LF")
      )
      (libsource (lib "BSPD_Schlib") (part "50K可變垂直-3296W-1-503LF"))
    )
    (comp (ref "R32")
      (value "39kR")
      (footprint "0805-Resistor")
      (description "CRCW Thick Film Commodity Chip Resistor 0805 Size 39K Ohm 1% 0.125 W 100 ppm/K 2-Pin SMD Paper T/R")
      (fields
        (field (name "MANUFACTURER") "Vishay")
        (field (name "MANUFACTURER PART NUMBER") "CRCW080539K0FKEAC")
      )
      (libsource (lib "BSPD_Schlib") (part "39k-CRCW080539K0FKEAC"))
    )
    (comp (ref "R33")
      (value "100R")
      (footprint "0805-Resistor")
      (description "Res Thick Film 0805 100 Ohm 1% 1/8W ±100ppm/°C Molded SMD Paper T/R")
      (fields
        (field (name "MANUFACTURER") "Vishay")
        (field (name "MANUFACTURER PART NUMBER") "CRCW0805100RFKEAC")
      )
      (libsource (lib "altium-import") (part "root_0_100-CRCW0805100RFKEAC_"))
    )
    (comp (ref "R34")
      (value "470R")
      (footprint "0805-Resistor")
      (description "Res Thick Film 0805 470 Ohm 1% 1/8W ±100ppm/°C Molded SMD Paper T/R")
      (fields
        (field (name "MANUFACTURER") "Vishay")
        (field (name "MANUFACTURER PART NUMBER") "CRCW0805470RFKEAC")
      )
      (libsource (lib "BSPD_Schlib") (part "470-CRCW0805470RFKEAC"))
    )
    (comp (ref "R35")
      (value "2kR")
      (footprint "2kR")
      (description "High Precision-High Stability Chip Resistor Thin Film 0805 2kOhm 1% Paper T/R")
      (fields
        (field (name "MANUFACTURER") "Yageo")
        (field (name "MANUFACTURER PART NUMBER") "RT0805FRE102KL")
      )
      (libsource (lib "shutdown_circuit") (part "RT0805FRE102KL"))
    )
    (comp (ref "R36")
      (value "100kR")
      (footprint "Yageo 0805")
      (description "Res Thin Film 0805 10K Ohm 1% 0.125W(1/8W) ±50ppm/C Molded SMD Paper T/R")
      (fields
        (field (name "MANUFACTURER") "Yageo")
        (field (name "MANUFACTURER PART NUMBER") "RT0805FRE1310KL")
      )
      (libsource (lib "shutdown_circuit") (part "RT0805FRE1310KL"))
    )
    (comp (ref "R37")
      (value "50kR")
      (footprint "50kR-vertical")
      (description "Trimmer; Cermet; Rest 50 Kilohms; PCB; Pwr-Rtg 0.5W; Dim 0.375InLx0.19InWx0.395InH")
      (fields
        (field (name "MANUFACTURER") "Bourns")
        (field (name "MANUFACTURER PART NUMBER") "3296W-1-503LF")
      )
      (libsource (lib "BSPD_Schlib") (part "50K可變垂直-3296W-1-503LF"))
    )
    (comp (ref "R38")
      (value "39kR")
      (footprint "0805-Resistor")
      (description "CRCW Thick Film Commodity Chip Resistor 0805 Size 39K Ohm 1% 0.125 W 100 ppm/K 2-Pin SMD Paper T/R")
      (fields
        (field (name "MANUFACTURER") "Vishay")
        (field (name "MANUFACTURER PART NUMBER") "CRCW080539K0FKEAC")
      )
      (libsource (lib "BSPD_Schlib") (part "39k-CRCW080539K0FKEAC"))
    )
    (comp (ref "R39")
      (value "115R")
      (footprint "Yageo 0805")
      (description "High Precision-High Stability Chip Resistor Thin Film 0805 115Ohm 0.5% Paper T/R")
      (fields
        (field (name "MANUFACTURER") "Yageo")
        (field (name "MANUFACTURER PART NUMBER") "RT0805DRE07115RL")
      )
      (libsource (lib "wheelspeed") (part "RT0805DRE07115RL"))
    )
    (comp (ref "R40")
      (value "4.7KΩ (4701) ±1%")
      (footprint "0805_R")
      (description "贴片电阻")
      (libsource (lib "wheelspeed") (part "0805 4.7KΩ (4701) 1%"))
    )
    (comp (ref "R41")
      (value "10KΩ (1002) ±1%")
      (footprint "0805_R")
      (description "贴片电阻")
      (libsource (lib "") (part "0805 10KΩ (1002) 1%_1"))
    )
    (comp (ref "R42")
      (value "39KΩ (3902) ±1%")
      (footprint "0805_R")
      (description "贴片电阻")
      (libsource (lib "wheelspeed") (part "0805 39KΩ (3902) 1%"))
    )
    (comp (ref "R43")
      (value "10KΩ (1002) ±1%")
      (footprint "0805_R")
      (description "贴片电阻")
      (libsource (lib "4wheel sensor board") (part "0805 10KΩ (1002) 1%"))
    )
    (comp (ref "R44")
      (value "2.2KΩ (2201) ±1%")
      (footprint "0805_R")
      (description "贴片电阻")
      (libsource (lib "wheelspeed") (part "0805 2.2KΩ (2201) 1%"))
    )
    (comp (ref "R45")
      (value "470KΩ (4703) ±1%")
      (footprint "0805_R")
      (description "贴片电阻")
      (libsource (lib "wheelspeed") (part "0805 470KΩ (4703) 1%"))
    )
    (comp (ref "R46")
      (value "47KΩ (4702) ±1%")
      (footprint "0805_R")
      (description "贴片电阻")
      (libsource (lib "wheelspeed") (part "0805 47KΩ (4702) 1%"))
    )
    (comp (ref "R47")
      (value "47KΩ (4702) ±1%")
      (footprint "0805_R")
      (description "贴片电阻")
      (libsource (lib "wheelspeed") (part "0805 47KΩ (4702) 1%"))
    )
    (comp (ref "R48")
      (value "200kR")
      (footprint "0805-Resistor")
      (description "CRCW Thick Film Commodity Chip Resistor 0805 Size 39K Ohm 1% 0.125 W 100 ppm/K 2-Pin SMD Paper T/R")
      (fields
        (field (name "MANUFACTURER") "Vishay")
        (field (name "MANUFACTURER PART NUMBER") "CRCW080539K0FKEAC")
      )
      (libsource (lib "BSPD_Schlib") (part "39k-CRCW080539K0FKEAC"))
    )
    (comp (ref "R49")
      (value "1MR")
      (footprint "0805-Resistor")
      (description "CRCW Thick Film Commodity Chip Resistor 0805 Size 39K Ohm 1% 0.125 W 100 ppm/K 2-Pin SMD Paper T/R")
      (fields
        (field (name "MANUFACTURER") "Vishay")
        (field (name "MANUFACTURER PART NUMBER") "CRCW080539K0FKEAC")
      )
      (libsource (lib "BSPD_Schlib") (part "39k-CRCW080539K0FKEAC"))
    )
    (comp (ref "R50")
      (value "270kR")
      (footprint "0805-Resistor")
      (description "CRCW Thick Film Commodity Chip Resistor 0805 Size 39K Ohm 1% 0.125 W 100 ppm/K 2-Pin SMD Paper T/R")
      (fields
        (field (name "MANUFACTURER") "Vishay")
        (field (name "MANUFACTURER PART NUMBER") "CRCW080539K0FKEAC")
      )
      (libsource (lib "BSPD_Schlib") (part "39k-CRCW080539K0FKEAC"))
    )
    (comp (ref "R51")
      (value "50kR")
      (footprint "50kR-vertical")
      (description "Trimmer; Cermet; Rest 50 Kilohms; PCB; Pwr-Rtg 0.5W; Dim 0.375InLx0.19InWx0.395InH")
      (fields
        (field (name "MANUFACTURER") "Bourns")
        (field (name "MANUFACTURER PART NUMBER") "3296W-1-503LF")
      )
      (libsource (lib "BSPD_Schlib") (part "50K可變垂直-3296W-1-503LF"))
    )
    (comp (ref "R52")
      (value "100kR")
      (footprint "0805-Resistor")
      (description "Res Thick Film 0805 100K Ohm 1% 1/8W ±100ppm/°C Molded SMD Paper T/R")
      (fields
        (field (name "MANUFACTURER") "Vishay")
        (field (name "MANUFACTURER PART NUMBER") "CRCW0805100KFKEAC")
      )
      (libsource (lib "BSPD_Schlib") (part "100k-CRCW0805100KFKEAC"))
    )
    (comp (ref "R53")
      (value "5kR")
      (footprint "0805-Resistor")
      (description "Res Thick Film 0805 470 Ohm 1% 1/8W ±100ppm/°C Molded SMD Paper T/R")
      (fields
        (field (name "MANUFACTURER") "Vishay")
        (field (name "MANUFACTURER PART NUMBER") "CRCW0805470RFKEAC")
      )
      (libsource (lib "BSPD_Schlib") (part "470-CRCW0805470RFKEAC"))
    )
    (comp (ref "R54")
      (value "100kR")
      (footprint "0805-Resistor")
      (description "Res Thick Film 0805 470 Ohm 1% 1/8W ±100ppm/°C Molded SMD Paper T/R")
      (fields
        (field (name "MANUFACTURER") "Vishay")
        (field (name "MANUFACTURER PART NUMBER") "CRCW0805470RFKEAC")
      )
      (libsource (lib "BSPD_Schlib") (part "470-CRCW0805470RFKEAC"))
    )
    (comp (ref "R55")
      (value "50kR")
      (footprint "50kR-vertical")
      (description "Trimmer; Cermet; Rest 50 Kilohms; PCB; Pwr-Rtg 0.5W; Dim 0.375InLx0.19InWx0.395InH")
      (fields
        (field (name "MANUFACTURER") "Bourns")
        (field (name "MANUFACTURER PART NUMBER") "3296W-1-503LF")
      )
      (libsource (lib "BSPD_Schlib") (part "50K可變垂直-3296W-1-503LF"))
    )
    (comp (ref "R56")
      (value "5kR")
      (footprint "0805-Resistor")
      (description "Res Thick Film 0805 470 Ohm 1% 1/8W ±100ppm/°C Molded SMD Paper T/R")
      (fields
        (field (name "MANUFACTURER") "Vishay")
        (field (name "MANUFACTURER PART NUMBER") "CRCW0805470RFKEAC")
      )
      (libsource (lib "BSPD_Schlib") (part "470-CRCW0805470RFKEAC"))
    )
    (comp (ref "R57")
      (value "10kR")
      (footprint "0805-Resistor")
      (description "Res Thick Film 0805 470 Ohm 1% 1/8W ±100ppm/°C Molded SMD Paper T/R")
      (fields
        (field (name "MANUFACTURER") "Vishay")
        (field (name "MANUFACTURER PART NUMBER") "CRCW0805470RFKEAC")
      )
      (libsource (lib "BSPD_Schlib") (part "470-CRCW0805470RFKEAC"))
    )
    (comp (ref "R58")
      (value "10kR")
      (footprint "0805-Resistor")
      (description "Res Thick Film 0805 470 Ohm 1% 1/8W ±100ppm/°C Molded SMD Paper T/R")
      (fields
        (field (name "MANUFACTURER") "Vishay")
        (field (name "MANUFACTURER PART NUMBER") "CRCW0805470RFKEAC")
      )
      (libsource (lib "BSPD_Schlib") (part "470-CRCW0805470RFKEAC"))
    )
    (comp (ref "R59")
      (value "432R")
      (footprint "432R")
      (description "Res Thin Film 0805 432 Ohm 1% 1/8W ±50ppm/°C Molded SMD SMD Paper T/R")
      (fields
        (field (name "MANUFACTURER") "Yageo")
        (field (name "MANUFACTURER PART NUMBER") "RT0805FRE07432RL")
      )
      (libsource (lib "shutdown_circuit") (part "RT0805FRE07432RL"))
    )
    (comp (ref "R60")
      (value "100R(4.7kR)")
      (footprint "4.99kR")
      (description "Res Thin Film 0805 4.99K Ohm 0.5% 1/8W ±50ppm/°C Molded SMD Paper T/R")
      (fields
        (field (name "MANUFACTURER") "Yageo")
        (field (name "MANUFACTURER PART NUMBER") "RT0805DRE074K99L")
      )
      (libsource (lib "shutdown_circuit") (part "RT0805DRE074K99L"))
    )
    (comp (ref "R61")
      (value "10kR")
      (footprint "Yageo 0805")
      (description "Res High Precision Thin Film 0805 11k Ohm 0.5% 1/8W ±50ppm/°C Molded Paper T/R")
      (fields
        (field (name "MANUFACTURER") "Yageo")
        (field (name "MANUFACTURER PART NUMBER") "RT0805DRE0711KL")
      )
      (libsource (lib "shutdown_circuit") (part "RT0805DRE0711KL"))
    )
    (comp (ref "R62")
      (value "50kR")
      (footprint "50kR-vertical")
      (description "Trimmer; Cermet; Rest 50 Kilohms; PCB; Pwr-Rtg 0.5W; Dim 0.375InLx0.19InWx0.395InH")
      (fields
        (field (name "MANUFACTURER") "Bourns")
        (field (name "MANUFACTURER PART NUMBER") "3296W-1-503LF")
      )
      (libsource (lib "BSPD_Schlib") (part "50K可變垂直-3296W-1-503LF"))
    )
    (comp (ref "R63")
      (value "1kR")
      (footprint "0805-Resistor")
      (description "Res Thick Film 0805 100K Ohm 1% 1/8W ±100ppm/°C Molded SMD Paper T/R")
      (fields
        (field (name "MANUFACTURER") "Vishay")
        (field (name "MANUFACTURER PART NUMBER") "CRCW0805100KFKEAC")
      )
      (libsource (lib "BSPD_Schlib_1") (part "100k-CRCW0805100KFKEAC"))
    )
    (comp (ref "R64")
      (value "100R")
      (footprint "0805-Resistor")
      (description "Res Thick Film 0805 100K Ohm 1% 1/8W ±100ppm/°C Molded SMD Paper T/R")
      (fields
        (field (name "MANUFACTURER") "Vishay")
        (field (name "MANUFACTURER PART NUMBER") "CRCW0805100KFKEAC")
      )
      (libsource (lib "BSPD_Schlib_1") (part "100k-CRCW0805100KFKEAC"))
    )
    (comp (ref "R65")
      (value "100kR")
      (footprint "0805-Resistor")
      (description "Res Thick Film 0805 100K Ohm 1% 1/8W ±100ppm/°C Molded SMD Paper T/R")
      (fields
        (field (name "MANUFACTURER") "Vishay")
        (field (name "MANUFACTURER PART NUMBER") "CRCW0805100KFKEAC")
      )
      (libsource (lib "BSPD_Schlib_1") (part "100k-CRCW0805100KFKEAC"))
    )
    (comp (ref "R66")
      (value "432R")
      (footprint "432R")
      (description "Res Thin Film 0805 432 Ohm 1% 1/8W ±50ppm/°C Molded SMD SMD Paper T/R")
      (fields
        (field (name "MANUFACTURER") "Yageo")
        (field (name "MANUFACTURER PART NUMBER") "RT0805FRE07432RL")
      )
      (libsource (lib "shutdown_circuit") (part "RT0805FRE07432RL"))
    )
    (comp (ref "R67")
      (value "100R")
      (footprint "4.99kR")
      (description "Res Thin Film 0805 4.99K Ohm 0.5% 1/8W ±50ppm/°C Molded SMD Paper T/R")
      (fields
        (field (name "MANUFACTURER") "Yageo")
        (field (name "MANUFACTURER PART NUMBER") "RT0805DRE074K99L")
      )
      (libsource (lib "shutdown_circuit") (part "RT0805DRE074K99L"))
    )
    (comp (ref "R68")
      (value "10kR")
      (footprint "Yageo 0805")
      (description "Res High Precision Thin Film 0805 11k Ohm 0.5% 1/8W ±50ppm/°C Molded Paper T/R")
      (fields
        (field (name "MANUFACTURER") "Yageo")
        (field (name "MANUFACTURER PART NUMBER") "RT0805DRE0711KL")
      )
      (libsource (lib "shutdown_circuit") (part "RT0805DRE0711KL"))
    )
    (comp (ref "R69")
      (value "50kR")
      (footprint "50kR-vertical")
      (description "Trimmer; Cermet; Rest 50 Kilohms; PCB; Pwr-Rtg 0.5W; Dim 0.375InLx0.19InWx0.395InH")
      (fields
        (field (name "MANUFACTURER") "Bourns")
        (field (name "MANUFACTURER PART NUMBER") "3296W-1-503LF")
      )
      (libsource (lib "BSPD_Schlib") (part "50K可變垂直-3296W-1-503LF"))
    )
    (comp (ref "R70")
      (value "1kR")
      (footprint "0805-Resistor")
      (description "Res Thick Film 0805 100K Ohm 1% 1/8W ±100ppm/°C Molded SMD Paper T/R")
      (fields
        (field (name "MANUFACTURER") "Vishay")
        (field (name "MANUFACTURER PART NUMBER") "CRCW0805100KFKEAC")
      )
      (libsource (lib "BSPD_Schlib_1") (part "100k-CRCW0805100KFKEAC"))
    )
    (comp (ref "R71")
      (value "100R")
      (footprint "0805-Resistor")
      (description "Res Thick Film 0805 100K Ohm 1% 1/8W ±100ppm/°C Molded SMD Paper T/R")
      (fields
        (field (name "MANUFACTURER") "Vishay")
        (field (name "MANUFACTURER PART NUMBER") "CRCW0805100KFKEAC")
      )
      (libsource (lib "BSPD_Schlib_1") (part "100k-CRCW0805100KFKEAC"))
    )
    (comp (ref "R72")
      (value "100kR")
      (footprint "0805-Resistor")
      (description "Res Thick Film 0805 100K Ohm 1% 1/8W ±100ppm/°C Molded SMD Paper T/R")
      (fields
        (field (name "MANUFACTURER") "Vishay")
        (field (name "MANUFACTURER PART NUMBER") "CRCW0805100KFKEAC")
      )
      (libsource (lib "BSPD_Schlib_1") (part "100k-CRCW0805100KFKEAC"))
    )
    (comp (ref "R73")
      (value "432R")
      (footprint "432R")
      (description "Res Thin Film 0805 432 Ohm 1% 1/8W ±50ppm/°C Molded SMD SMD Paper T/R")
      (fields
        (field (name "MANUFACTURER") "Yageo")
        (field (name "MANUFACTURER PART NUMBER") "RT0805FRE07432RL")
      )
      (libsource (lib "shutdown_circuit") (part "RT0805FRE07432RL"))
    )
    (comp (ref "R74")
      (value "100R")
      (footprint "4.99kR")
      (description "Res Thin Film 0805 4.99K Ohm 0.5% 1/8W ±50ppm/°C Molded SMD Paper T/R")
      (fields
        (field (name "MANUFACTURER") "Yageo")
        (field (name "MANUFACTURER PART NUMBER") "RT0805DRE074K99L")
      )
      (libsource (lib "shutdown_circuit") (part "RT0805DRE074K99L"))
    )
    (comp (ref "R75")
      (value "10kR")
      (footprint "Yageo 0805")
      (description "Res High Precision Thin Film 0805 11k Ohm 0.5% 1/8W ±50ppm/°C Molded Paper T/R")
      (fields
        (field (name "MANUFACTURER") "Yageo")
        (field (name "MANUFACTURER PART NUMBER") "RT0805DRE0711KL")
      )
      (libsource (lib "shutdown_circuit") (part "RT0805DRE0711KL"))
    )
    (comp (ref "R76")
      (value "50kR")
      (footprint "50kR-vertical")
      (description "Trimmer; Cermet; Rest 50 Kilohms; PCB; Pwr-Rtg 0.5W; Dim 0.375InLx0.19InWx0.395InH")
      (fields
        (field (name "MANUFACTURER") "Bourns")
        (field (name "MANUFACTURER PART NUMBER") "3296W-1-503LF")
      )
      (libsource (lib "BSPD_Schlib") (part "50K可變垂直-3296W-1-503LF"))
    )
    (comp (ref "R77")
      (value "1kR")
      (footprint "0805-Resistor")
      (description "Res Thick Film 0805 100K Ohm 1% 1/8W ±100ppm/°C Molded SMD Paper T/R")
      (fields
        (field (name "MANUFACTURER") "Vishay")
        (field (name "MANUFACTURER PART NUMBER") "CRCW0805100KFKEAC")
      )
      (libsource (lib "BSPD_Schlib_1") (part "100k-CRCW0805100KFKEAC"))
    )
    (comp (ref "R78")
      (value "100R")
      (footprint "0805-Resistor")
      (description "Res Thick Film 0805 100K Ohm 1% 1/8W ±100ppm/°C Molded SMD Paper T/R")
      (fields
        (field (name "MANUFACTURER") "Vishay")
        (field (name "MANUFACTURER PART NUMBER") "CRCW0805100KFKEAC")
      )
      (libsource (lib "BSPD_Schlib_1") (part "100k-CRCW0805100KFKEAC"))
    )
    (comp (ref "R79")
      (value "100kR")
      (footprint "0805-Resistor")
      (description "Res Thick Film 0805 100K Ohm 1% 1/8W ±100ppm/°C Molded SMD Paper T/R")
      (fields
        (field (name "MANUFACTURER") "Vishay")
        (field (name "MANUFACTURER PART NUMBER") "CRCW0805100KFKEAC")
      )
      (libsource (lib "BSPD_Schlib_1") (part "100k-CRCW0805100KFKEAC"))
    )
    (comp (ref "R80")
      (value "665R")
      (footprint "665R,499R")
      (description "Res Thin Film 0805 665 Ohm 0.1% 1/8W ±25ppm/°C Molded SMD Paper T/R")
      (fields
        (field (name "MANUFACTURER") "TE Connectivity")
        (field (name "MANUFACTURER PART NUMBER") "RP73PF2A665RBTDF")
      )
      (libsource (lib "shutdown_circuit") (part "RP73PF2A665RBTDF"))
    )
    (comp (ref "R81")
      (value "665R")
      (footprint "665R,499R")
      (description "Res Thin Film 0805 665 Ohm 0.1% 1/8W ±25ppm/°C Molded SMD Paper T/R")
      (fields
        (field (name "MANUFACTURER") "TE Connectivity")
        (field (name "MANUFACTURER PART NUMBER") "RP73PF2A665RBTDF")
      )
      (libsource (lib "shutdown_circuit") (part "RP73PF2A665RBTDF"))
    )
    (comp (ref "R82")
      (value "665R")
      (footprint "665R,499R")
      (description "Res Thin Film 0805 665 Ohm 0.1% 1/8W ±25ppm/°C Molded SMD Paper T/R")
      (fields
        (field (name "MANUFACTURER") "TE Connectivity")
        (field (name "MANUFACTURER PART NUMBER") "RP73PF2A665RBTDF")
      )
      (libsource (lib "shutdown_circuit") (part "RP73PF2A665RBTDF"))
    )
    (comp (ref "R83")
      (value "549kR")
      (footprint "0805-Resistor")
      (description "Res Thick Film 0805 470 Ohm 1% 1/8W ±100ppm/°C Molded SMD Paper T/R")
      (fields
        (field (name "MANUFACTURER") "Vishay")
        (field (name "MANUFACTURER PART NUMBER") "CRCW0805470RFKEAC")
      )
      (libsource (lib "BSPD_Schlib") (part "470-CRCW0805470RFKEAC"))
    )
    (comp (ref "R84")
      (value "47kR")
      (footprint "0805-Resistor")
      (description "Res Thick Film 0805 470 Ohm 1% 1/8W ±100ppm/°C Molded SMD Paper T/R")
      (fields
        (field (name "MANUFACTURER") "Vishay")
        (field (name "MANUFACTURER PART NUMBER") "CRCW0805470RFKEAC")
      )
      (libsource (lib "BSPD_Schlib") (part "470-CRCW0805470RFKEAC"))
    )
    (comp (ref "R85")
      (value "510R")
      (footprint "0805-Resistor")
      (description "Res Thick Film 0805 470 Ohm 1% 1/8W ±100ppm/°C Molded SMD Paper T/R")
      (fields
        (field (name "MANUFACTURER") "Vishay")
        (field (name "MANUFACTURER PART NUMBER") "CRCW0805470RFKEAC")
      )
      (libsource (lib "BSPD_Schlib") (part "470-CRCW0805470RFKEAC"))
    )
    (comp (ref "R86")
      (value "430R")
      (footprint "0805-Resistor")
      (description "Res Thick Film 0805 470 Ohm 1% 1/8W ±100ppm/°C Molded SMD Paper T/R")
      (fields
        (field (name "MANUFACTURER") "Vishay")
        (field (name "MANUFACTURER PART NUMBER") "CRCW0805470RFKEAC")
      )
      (libsource (lib "BSPD_Schlib") (part "470-CRCW0805470RFKEAC"))
    )
    (comp (ref "R87")
      (value "10kR")
      (footprint "0805-Resistor")
      (description "Res Thick Film 0805 470 Ohm 1% 1/8W ±100ppm/°C Molded SMD Paper T/R")
      (fields
        (field (name "MANUFACTURER") "Vishay")
        (field (name "MANUFACTURER PART NUMBER") "CRCW0805470RFKEAC")
      )
      (libsource (lib "BSPD_Schlib") (part "470-CRCW0805470RFKEAC"))
    )
    (comp (ref "R88")
      (value "10MR")
      (footprint "0805-Resistor")
      (description "Res Thick Film 0805 470 Ohm 1% 1/8W ±100ppm/°C Molded SMD Paper T/R")
      (fields
        (field (name "MANUFACTURER") "Vishay")
        (field (name "MANUFACTURER PART NUMBER") "CRCW0805470RFKEAC")
      )
      (libsource (lib "BSPD_Schlib") (part "470-CRCW0805470RFKEAC"))
    )
    (comp (ref "R89")
      (value "470R")
      (footprint "0805-Resistor")
      (description "Res Thick Film 0805 470 Ohm 1% 1/8W ±100ppm/°C Molded SMD Paper T/R")
      (fields
        (field (name "MANUFACTURER") "Vishay")
        (field (name "MANUFACTURER PART NUMBER") "CRCW0805470RFKEAC")
      )
      (libsource (lib "BSPD_Schlib") (part "470-CRCW0805470RFKEAC"))
    )
    (comp (ref "R90")
      (value "10kR")
      (footprint "0805-Resistor")
      (description "Res Thick Film 0805 470 Ohm 1% 1/8W ±100ppm/°C Molded SMD Paper T/R")
      (fields
        (field (name "MANUFACTURER") "Vishay")
        (field (name "MANUFACTURER PART NUMBER") "CRCW0805470RFKEAC")
      )
      (libsource (lib "BSPD_Schlib") (part "470-CRCW0805470RFKEAC"))
    )
    (comp (ref "R91")
      (value "1k")
      (footprint "0805-Resistor")
      (description "Res Thick Film 0805 470 Ohm 1% 1/8W ±100ppm/°C Molded SMD Paper T/R")
      (fields
        (field (name "MANUFACTURER") "Vishay")
        (field (name "MANUFACTURER PART NUMBER") "CRCW0805470RFKEAC")
      )
      (libsource (lib "BSPD_Schlib") (part "470-CRCW0805470RFKEAC"))
    )
    (comp (ref "R92")
      (value "0R")
      (footprint "0805-Resistor")
      (description "CRCW Thick Film Commodity Chip Resistor 0805 Size 39K Ohm 1% 0.125 W 100 ppm/K 2-Pin SMD Paper T/R")
      (fields
        (field (name "MANUFACTURER") "Vishay")
        (field (name "MANUFACTURER PART NUMBER") "CRCW080539K0FKEAC")
      )
      (libsource (lib "BSPD_Schlib") (part "39k-CRCW080539K0FKEAC"))
    )
    (comp (ref "R93")
      (value "10kR")
      (footprint "0805-Resistor")
      (description "CRCW Thick Film Commodity Chip Resistor 0805 Size 39K Ohm 1% 0.125 W 100 ppm/K 2-Pin SMD Paper T/R")
      (fields
        (field (name "MANUFACTURER") "Vishay")
        (field (name "MANUFACTURER PART NUMBER") "CRCW080539K0FKEAC")
      )
      (libsource (lib "BSPD_Schlib") (part "39k-CRCW080539K0FKEAC"))
    )
    (comp (ref "R94")
      (value "39kR")
      (footprint "0805-Resistor")
      (description "CRCW Thick Film Commodity Chip Resistor 0805 Size 39K Ohm 1% 0.125 W 100 ppm/K 2-Pin SMD Paper T/R")
      (fields
        (field (name "MANUFACTURER") "Vishay")
        (field (name "MANUFACTURER PART NUMBER") "CRCW080539K0FKEAC")
      )
      (libsource (lib "BSPD_Schlib") (part "39k-CRCW080539K0FKEAC"))
    )
    (comp (ref "R95")
      (value "100k")
      (footprint "0805-Resistor")
      (description "Res Thick Film 0805 100K Ohm 1% 1/8W ±100ppm/°C Molded SMD Paper T/R")
      (fields
        (field (name "MANUFACTURER") "Vishay")
        (field (name "MANUFACTURER PART NUMBER") "CRCW0805100KFKEAC")
      )
      (libsource (lib "BSPD_Schlib_1") (part "100k-CRCW0805100KFKEAC"))
    )
    (comp (ref "R96")
      (value "51k")
      (footprint "0805-Resistor")
      (description "Res Thick Film 0805 100K Ohm 1% 1/8W ±100ppm/°C Molded SMD Paper T/R")
      (fields
        (field (name "MANUFACTURER") "Vishay")
        (field (name "MANUFACTURER PART NUMBER") "CRCW0805100KFKEAC")
      )
      (libsource (lib "BSPD_Schlib_1") (part "100k-CRCW0805100KFKEAC"))
    )
    (comp (ref "R97")
      (value "100k")
      (footprint "0805-Resistor")
      (description "Res Thick Film 0805 100K Ohm 1% 1/8W ±100ppm/°C Molded SMD Paper T/R")
      (fields
        (field (name "MANUFACTURER") "Vishay")
        (field (name "MANUFACTURER PART NUMBER") "CRCW0805100KFKEAC")
      )
      (libsource (lib "BSPD_Schlib_1") (part "100k-CRCW0805100KFKEAC"))
    )
    (comp (ref "R98")
      (value "51k")
      (footprint "0805-Resistor")
      (description "Res Thick Film 0805 100K Ohm 1% 1/8W ±100ppm/°C Molded SMD Paper T/R")
      (fields
        (field (name "MANUFACTURER") "Vishay")
        (field (name "MANUFACTURER PART NUMBER") "CRCW0805100KFKEAC")
      )
      (libsource (lib "BSPD_Schlib_1") (part "100k-CRCW0805100KFKEAC"))
    )
    (comp (ref "R99")
      (value "100k")
      (footprint "0805-Resistor")
      (description "Res Thick Film 0805 100K Ohm 1% 1/8W ±100ppm/°C Molded SMD Paper T/R")
      (fields
        (field (name "MANUFACTURER") "Vishay")
        (field (name "MANUFACTURER PART NUMBER") "CRCW0805100KFKEAC")
      )
      (libsource (lib "BSPD_Schlib_1") (part "100k-CRCW0805100KFKEAC"))
    )
    (comp (ref "R100")
      (value "51k")
      (footprint "0805-Resistor")
      (description "Res Thick Film 0805 100K Ohm 1% 1/8W ±100ppm/°C Molded SMD Paper T/R")
      (fields
        (field (name "MANUFACTURER") "Vishay")
        (field (name "MANUFACTURER PART NUMBER") "CRCW0805100KFKEAC")
      )
      (libsource (lib "BSPD_Schlib_1") (part "100k-CRCW0805100KFKEAC"))
    )
    (comp (ref "R101")
      (value "470R")
      (footprint "0805-Resistor")
      (description "Res Thick Film 0805 470 Ohm 1% 1/8W ±100ppm/°C Molded SMD Paper T/R")
      (fields
        (field (name "MANUFACTURER") "Vishay")
        (field (name "MANUFACTURER PART NUMBER") "CRCW0805470RFKEAC")
      )
      (libsource (lib "BSPD_Schlib") (part "470-CRCW0805470RFKEAC"))
    )
    (comp (ref "R102")
      (value "100kR")
      (footprint "0805-Resistor")
      (description "Res Thick Film 0805 100K Ohm 1% 1/8W ±100ppm/°C Molded SMD Paper T/R")
      (fields
        (field (name "MANUFACTURER") "Vishay")
        (field (name "MANUFACTURER PART NUMBER") "CRCW0805100KFKEAC")
      )
      (libsource (lib "BSPD_Schlib") (part "100k-CRCW0805100KFKEAC"))
    )
    (comp (ref "re1")
      (value "G2RL-2A4-DC12")
      (footprint "G2RL-2A4-DC12")
      (description "Power Relay 12VDC 8A DPST-NO( (29mm 12.7mm 15.7mm)) THT")
      (fields (field (name "MANUFACTURER") "Omron"))
      (libsource (lib "shutdown_circuit") (part "G2RL-2A4-DC12"))
    )
    (comp (ref "re2")
      (value "G2RL-2A4-DC12")
      (footprint "G2RL-2A4-DC12")
      (description "Power Relay 12VDC 8A DPST-NO( (29mm 12.7mm 15.7mm)) THT")
      (fields (field (name "MANUFACTURER") "Omron"))
      (libsource (lib "shutdown_circuit") (part "G2RL-2A4-DC12"))
    )
    (comp (ref "re3")
      (value "G2RL-2A4-DC12")
      (footprint "G2RL-2A4-DC12")
      (description "Power Relay 12VDC 8A DPST-NO( (29mm 12.7mm 15.7mm)) THT")
      (fields (field (name "MANUFACTURER") "Omron"))
      (libsource (lib "shutdown_circuit") (part "G2RL-2A4-DC12"))
    )
    (comp (ref "SW1")
      (value "PTS526 SK08 SMTR2 LFS")
      (footprint "PTS526SKG15SMTR2LFS")
      (description "Switch Tactile N.O. SPST Flush Round Button Gull Wing 0.05A 12VDC 200000Cycles 2.45N SMD T/R")
      (fields (field (name "MANUFACTURER") "C&K Components"))
      (libsource (lib "BSPD_Schlib") (part "PTS526 SK08 SMTR2 LFS"))
    )
    (comp (ref "SW2")
      (value "PTS526 SK08 SMTR2 LFS")
      (footprint "PTS526SKG15SMTR2LFS")
      (description "Switch Tactile N.O. SPST Flush Round Button Gull Wing 0.05A 12VDC 200000Cycles 2.45N SMD T/R")
      (fields (field (name "MANUFACTURER") "C&K Components"))
      (libsource (lib "BSPD_Schlib") (part "PTS526 SK08 SMTR2 LFS"))
    )
    (comp (ref "SW3")
      (value "PTS526 SK08 SMTR2 LFS")
      (footprint "PTS526SKG15SMTR2LFS")
      (description "Switch Tactile N.O. SPST Flush Round Button Gull Wing 0.05A 12VDC 200000Cycles 2.45N SMD T/R")
      (fields (field (name "MANUFACTURER") "C&K Components"))
      (libsource (lib "BSPD_Schlib") (part "PTS526 SK08 SMTR2 LFS"))
    )
    (comp (ref "U1")
      (value "CD4041UBM96")
      (footprint "CD4041UBM96:SOIC127P600X175-14N")
      (description "Buffer 4-CH Inverting/Non-Inverting Push-Pull CMOS 14-Pin SOIC-14 Tube")
      (fields
        (field (name "MANUFACTURER") "Texas Instruments")
        (field (name "MANUFACTURER PART NUMBER") "CD4041UBPW")
      )
      (libsource (lib "shutdown_circuit") (part "CD4041UBM96"))
    )
    (comp (ref "U2")
      (value "LTC6993CS6-2#TRMPBF")
      (footprint "TSOT-23_S6")
      (description "Monostable Multivibrator Single-Element 0°C 70°C Automotive 6-Pin TSOT-23 T/R")
      (fields (field (name "MANUFACTURER") "Analog Devices / Linear Technology"))
      (libsource (lib "BSPD_Schlib") (part "LTC6993CS6-2#TRMPBF"))
    )
    (comp (ref "U3")
      (value "LTC2644CMS-L12#PBF")
      (footprint "SOP65P490X110-12N")
      (description "Digital To Analog Converter Dac, Dual, 12 Bit, Msop-12")
      (fields (field (name "MANUFACTURER") "Analog Devices"))
      (libsource (lib "BSPD_Schlib") (part "LTC2644CMS-L12#PBF"))
    )
    (comp (ref "U4")
      (value "CD4041")
      (footprint "SOIC127P600X175-14N")
      (description "Buffer 4-CH Inverting/Non-Inverting Push-Pull CMOS 14-Pin SOIC-14 Tube")
      (libsource (lib "shutdown_circuit") (part "CD4041"))
    )
    (comp (ref "U5")
      (value "ADP7104ARDZ-5.0-R7")
      (footprint "SOIC127P600X175-9N")
      (description "Linear Voltage Regulator IC 1 Output 500mA 8-SOIC-EP")
      (fields (field (name "MF") "Analog Devices"))
      (libsource (lib "ADP7104ARDZ-5.0-R7") (part "ADP7104ARDZ-5.0-R7"))
    )
    (comp (ref "U6")
      (value "TPS259631DDAR")
      (footprint "VREG_LM5017MR/NOPB")
      (fields (field (name "MANUFACTURER") "Texas Instruments"))
      (libsource (lib "BSPD_Schlib") (part "TPS259631DDAR"))
    )
  )
  (nets
    (net (code "1") (name "/BSPD") (class "Default")
      (node (ref "H2") (pin "6") (pinfunction "6_6") (pintype "passive"))
      (node (ref "H3") (pin "2") (pinfunction "2_2") (pintype "passive"))
      (node (ref "IC2") (pin "10") (pinfunction "out_10") (pintype "passive"))
      (node (ref "R60") (pin "1") (pinfunction "83_1") (pintype "passive"))
    )
    (net (code "2") (name "/NetIC2_2") (class "Default")
      (node (ref "C89") (pin "2") (pinfunction "-_2") (pintype "passive"))
      (node (ref "IC2") (pin "2") (pinfunction "in_2") (pintype "passive"))
      (node (ref "R102") (pin "2") (pinfunction "2_2") (pintype "passive"))
    )
    (net (code "3") (name "/NetOP3_2") (class "Default")
      (node (ref "OP3") (pin "2") (pinfunction "out_2") (pintype "passive"))
      (node (ref "R102") (pin "1") (pinfunction "1_1") (pintype "passive"))
      (node (ref "R93") (pin "1") (pinfunction "1_1") (pintype "passive"))
    )
    (net (code "4") (name "/brake") (class "Default")
      (node (ref "C19") (pin "2") (pinfunction "2_2") (pintype "passive"))
      (node (ref "D3") (pin "2") (pinfunction "+_2") (pintype "passive"))
      (node (ref "D4") (pin "1") (pinfunction "-_1") (pintype "passive"))
      (node (ref "R24") (pin "2") (pinfunction "2_2") (pintype "passive"))
      (node (ref "R25") (pin "1") (pinfunction "1_1") (pintype "passive"))
      (node (ref "R26") (pin "1") (pinfunction "83_1") (pintype "passive"))
      (node (ref "R35") (pin "1") (pinfunction "83_1") (pintype "passive"))
      (node (ref "R53") (pin "2") (pinfunction "2_2") (pintype "passive"))
      (node (ref "R9") (pin "1") (pinfunction "1_1") (pintype "passive"))
    )
    (net (code "5") (name "/brake_HL") (class "Default")
      (node (ref "OP1") (pin "11") (pinfunction "+_11") (pintype "passive"))
      (node (ref "R8") (pin "2") (pinfunction "2_2") (pintype "passive"))
    )
    (net (code "6") (name "/brake_HLb") (class "Default")
      (node (ref "R11") (pin "2") (pinfunction "2_2") (pintype "passive"))
      (node (ref "R8") (pin "1") (pinfunction "1_1") (pintype "passive"))
    )
    (net (code "7") (name "/brake_LL") (class "Default")
      (node (ref "OP1") (pin "8") (pinfunction "-_8") (pintype "passive"))
      (node (ref "R10") (pin "2") (pinfunction "2_2") (pintype "passive"))
    )
    (net (code "8") (name "/brake_LLb") (class "Default")
      (node (ref "R10") (pin "1") (pinfunction "1_1") (pintype "passive"))
      (node (ref "R12") (pin "2") (pinfunction "2_2") (pintype "passive"))
    )
    (net (code "9") (name "/brake_init") (class "Default")
      (node (ref "H3") (pin "3") (pinfunction "3_3") (pintype "passive"))
      (node (ref "R24") (pin "1") (pinfunction "1_1") (pintype "passive"))
    )
    (net (code "10") (name "/brake_min") (class "Default")
      (node (ref "OP2") (pin "4") (pinfunction "-_4") (pintype "passive"))
      (node (ref "R27") (pin "2") (pinfunction "2_2") (pintype "passive"))
    )
    (net (code "11") (name "/brake_std") (class "Default")
      (node (ref "OP1") (pin "10") (pinfunction "-_10") (pintype "passive"))
      (node (ref "OP1") (pin "9") (pinfunction "+_9") (pintype "passive"))
      (node (ref "R9") (pin "2") (pinfunction "2_2") (pintype "passive"))
    )
    (net (code "12") (name "/current") (class "Default")
      (node (ref "C18") (pin "2") (pinfunction "2_2") (pintype "passive"))
      (node (ref "D1") (pin "2") (pinfunction "+_2") (pintype "passive"))
      (node (ref "D2") (pin "1") (pinfunction "-_1") (pintype "passive"))
      (node (ref "OP2") (pin "7") (pinfunction "+_7") (pintype "passive"))
      (node (ref "R2") (pin "1") (pinfunction "1_1") (pintype "passive"))
      (node (ref "R20") (pin "2") (pinfunction "2_2") (pintype "passive"))
      (node (ref "R21") (pin "1") (pinfunction "1_1") (pintype "passive"))
    )
    (net (code "13") (name "/current_HL") (class "Default")
      (node (ref "OP1") (pin "7") (pinfunction "+_7") (pintype "passive"))
      (node (ref "R1") (pin "2") (pinfunction "2_2") (pintype "passive"))
    )
    (net (code "14") (name "/current_HLb") (class "Default")
      (node (ref "R1") (pin "1") (pinfunction "1_1") (pintype "passive"))
      (node (ref "R4") (pin "2") (pinfunction "2_2") (pintype "passive"))
    )
    (net (code "15") (name "/current_LL") (class "Default")
      (node (ref "OP1") (pin "4") (pinfunction "-_4") (pintype "passive"))
      (node (ref "R3") (pin "2") (pinfunction "2_2") (pintype "passive"))
    )
    (net (code "16") (name "/current_LLb") (class "Default")
      (node (ref "R3") (pin "1") (pinfunction "1_1") (pintype "passive"))
      (node (ref "R5") (pin "2") (pinfunction "2_2") (pintype "passive"))
    )
    (net (code "17") (name "/current_init") (class "Default")
      (node (ref "H3") (pin "1") (pinfunction "1_1") (pintype "passive"))
      (node (ref "R20") (pin "1") (pinfunction "1_1") (pintype "passive"))
    )
    (net (code "18") (name "/current_min") (class "Default")
      (node (ref "OP2") (pin "6") (pinfunction "-_6") (pintype "passive"))
      (node (ref "R22") (pin "2") (pinfunction "2_2") (pintype "passive"))
    )
    (net (code "19") (name "/current_out1") (class "Default")
      (node (ref "IC1") (pin "1") (pinfunction "in_1") (pintype "passive"))
      (node (ref "IC1") (pin "5") (pinfunction "in_5") (pintype "passive"))
      (node (ref "LED6") (pin "1") (pinfunction "1_1") (pintype "passive"))
      (node (ref "OP1") (pin "1") (pinfunction "out_1") (pintype "passive"))
      (node (ref "OP1") (pin "2") (pinfunction "out_2") (pintype "passive"))
      (node (ref "R7") (pin "1") (pinfunction "1_1") (pintype "passive"))
    )
    (net (code "20") (name "/current_std") (class "Default")
      (node (ref "OP1") (pin "5") (pinfunction "+_5") (pintype "passive"))
      (node (ref "OP1") (pin "6") (pinfunction "-_6") (pintype "passive"))
      (node (ref "R2") (pin "2") (pinfunction "2_2") (pintype "passive"))
    )
    (net (code "22") (name "5V") (class "Default")
      (node (ref "C1") (pin "2") (pinfunction "2_2") (pintype "passive"))
      (node (ref "C10") (pin "2") (pinfunction "2_2") (pintype "passive"))
      (node (ref "C12") (pin "2") (pinfunction "2_2") (pintype "passive"))
      (node (ref "C13") (pin "2") (pinfunction "2_2") (pintype "passive"))
      (node (ref "C14") (pin "2") (pinfunction "2_2") (pintype "passive"))
      (node (ref "C17") (pin "2") (pinfunction "2_2") (pintype "passive"))
      (node (ref "C2") (pin "2") (pinfunction "2_2") (pintype "passive"))
      (node (ref "C20") (pin "2") (pinfunction "2_2") (pintype "passive"))
      (node (ref "C25") (pin "2") (pinfunction "2_2") (pintype "passive"))
      (node (ref "C26") (pin "2") (pinfunction "2_2") (pintype "passive"))
      (node (ref "C3") (pin "1") (pinfunction "+_1") (pintype "passive"))
      (node (ref "C5") (pin "2") (pinfunction "2_2") (pintype "passive"))
      (node (ref "C6") (pin "2") (pinfunction "2_2") (pintype "passive"))
      (node (ref "C89") (pin "1") (pinfunction "+_1") (pintype "passive"))
      (node (ref "C9") (pin "2") (pinfunction "2_2") (pintype "passive"))
      (node (ref "D1") (pin "1") (pinfunction "-_1") (pintype "passive"))
      (node (ref "D3") (pin "1") (pinfunction "-_1") (pintype "passive"))
      (node (ref "D5") (pin "1") (pinfunction "-_1") (pintype "passive"))
      (node (ref "IC1") (pin "14") (pinfunction "Vcc_14") (pintype "passive"))
      (node (ref "IC2") (pin "14") (pinfunction "Vcc_14") (pintype "passive"))
      (node (ref "LED2") (pin "2") (pinfunction "2_2") (pintype "passive"))
      (node (ref "OP1") (pin "3") (pinfunction "Vcc_3") (pintype "passive"))
      (node (ref "OP2") (pin "3") (pinfunction "Vcc_3") (pintype "passive"))
      (node (ref "OP3") (pin "3") (pinfunction "Vcc_3") (pintype "passive"))
      (node (ref "OP4") (pin "3") (pinfunction "Vcc_3") (pintype "passive"))
      (node (ref "R101") (pin "2") (pinfunction "2_2") (pintype "passive"))
      (node (ref "R11") (pin "1") (pinfunction "1_1") (pintype "passive"))
      (node (ref "R13") (pin "2") (pinfunction "2_2") (pintype "passive"))
      (node (ref "R14") (pin "2") (pinfunction "2_2") (pintype "passive"))
      (node (ref "R15") (pin "2") (pinfunction "2_2") (pintype "passive"))
      (node (ref "R17") (pin "2") (pinfunction "2_2") (pintype "passive"))
      (node (ref "R21") (pin "2") (pinfunction "2_2") (pintype "passive"))
      (node (ref "R22") (pin "1") (pinfunction "1_1") (pintype "passive"))
      (node (ref "R23") (pin "2") (pinfunction "2_2") (pintype "passive"))
      (node (ref "R25") (pin "2") (pinfunction "2_2") (pintype "passive"))
      (node (ref "R27") (pin "1") (pinfunction "1_1") (pintype "passive"))
      (node (ref "R29") (pin "2") (pinfunction "2_2") (pintype "passive"))
      (node (ref "R31") (pin "1") (pinfunction "1_1") (pintype "passive"))
      (node (ref "R32") (pin "2") (pinfunction "2_2") (pintype "passive"))
      (node (ref "R34") (pin "2") (pinfunction "2_2") (pintype "passive"))
      (node (ref "R37") (pin "1") (pinfunction "1_1") (pintype "passive"))
      (node (ref "R38") (pin "2") (pinfunction "2_2") (pintype "passive"))
      (node (ref "R4") (pin "1") (pinfunction "1_1") (pintype "passive"))
      (node (ref "R42") (pin "2") (pinfunction "2_2") (pintype "passive"))
      (node (ref "R44") (pin "2") (pinfunction "2_2") (pintype "passive"))
      (node (ref "R49") (pin "2") (pinfunction "2_2") (pintype "passive"))
      (node (ref "R51") (pin "1") (pinfunction "1_1") (pintype "passive"))
      (node (ref "R55") (pin "1") (pinfunction "1_1") (pintype "passive"))
      (node (ref "R56") (pin "1") (pinfunction "1_1") (pintype "passive"))
      (node (ref "R57") (pin "2") (pinfunction "2_2") (pintype "passive"))
      (node (ref "R6") (pin "2") (pinfunction "2_2") (pintype "passive"))
      (node (ref "R62") (pin "1") (pinfunction "1_1") (pintype "passive"))
      (node (ref "R63") (pin "2") (pinfunction "2_2") (pintype "passive"))
      (node (ref "R69") (pin "1") (pinfunction "1_1") (pintype "passive"))
      (node (ref "R7") (pin "2") (pinfunction "2_2") (pintype "passive"))
      (node (ref "R70") (pin "2") (pinfunction "2_2") (pintype "passive"))
      (node (ref "R76") (pin "1") (pinfunction "1_1") (pintype "passive"))
      (node (ref "R77") (pin "2") (pinfunction "2_2") (pintype "passive"))
      (node (ref "R89") (pin "2") (pinfunction "2_2") (pintype "passive"))
      (node (ref "R93") (pin "2") (pinfunction "2_2") (pintype "passive"))
      (node (ref "R94") (pin "2") (pinfunction "2_2") (pintype "passive"))
      (node (ref "SW1") (pin "1") (pinfunction "1_1") (pintype "passive"))
      (node (ref "SW2") (pin "1") (pinfunction "1_1") (pintype "passive"))
      (node (ref "SW3") (pin "1") (pinfunction "1_1") (pintype "passive"))
      (node (ref "U1") (pin "14") (pinfunction "VDD_14") (pintype "passive"))
      (node (ref "U2") (pin "5") (pinfunction "V+_5") (pintype "passive"))
      (node (ref "U3") (pin "1") (pinfunction "VCC_1") (pintype "passive"))
      (node (ref "U3") (pin "10") (pinfunction "REF_10") (pintype "passive"))
      (node (ref "U3") (pin "5") (pinfunction "IOVCC_5") (pintype "passive"))
      (node (ref "U3") (pin "7") (pinfunction "~{PD}_7") (pintype "passive"))
      (node (ref "U4") (pin "14") (pinfunction "Vdd_14") (pintype "passive"))
      (node (ref "U5") (pin "1") (pinfunction "VOUT_1") (pintype "output"))
      (node (ref "U5") (pin "2") (pinfunction "SENSE/ADJ_2") (pintype "passive"))
    )
    (net (code "23") (name "12V") (class "Default")
      (node (ref "C11") (pin "2") (pinfunction "2_2") (pintype "passive"))
      (node (ref "C16") (pin "2") (pinfunction "2_2") (pintype "passive"))
      (node (ref "C23") (pin "2") (pinfunction "2_2") (pintype "passive"))
      (node (ref "C27") (pin "1") (pinfunction "P_1") (pintype "passive"))
      (node (ref "D10") (pin "1") (pinfunction "-_1") (pintype "passive"))
      (node (ref "D7") (pin "1") (pinfunction "71_1") (pintype "passive"))
      (node (ref "D8") (pin "1") (pinfunction "71_1") (pintype "passive"))
      (node (ref "D9") (pin "1") (pinfunction "71_1") (pintype "passive"))
      (node (ref "H2") (pin "7") (pinfunction "7_7") (pintype "passive"))
      (node (ref "H3") (pin "5") (pinfunction "5_5") (pintype "passive"))
      (node (ref "R59") (pin "2") (pinfunction "84_2") (pintype "passive"))
      (node (ref "R66") (pin "2") (pinfunction "84_2") (pintype "passive"))
      (node (ref "R73") (pin "2") (pinfunction "84_2") (pintype "passive"))
      (node (ref "R83") (pin "2") (pinfunction "2_2") (pintype "passive"))
      (node (ref "U5") (pin "5") (pinfunction "EN/UVLO_5") (pintype "input"))
      (node (ref "U5") (pin "8") (pinfunction "VIN_8") (pintype "power_in"))
      (node (ref "U6") (pin "4") (pinfunction "IN_4") (pintype "passive"))
      (node (ref "re1") (pin "8") (pinfunction "121_8") (pintype "passive"))
      (node (ref "re2") (pin "8") (pinfunction "121_8") (pintype "passive"))
      (node (ref "re3") (pin "8") (pinfunction "121_8") (pintype "passive"))
    )
    (net (code "24") (name "AGND") (class "Default")
      (node (ref "C12") (pin "1") (pinfunction "1_1") (pintype "passive"))
      (node (ref "C13") (pin "1") (pinfunction "1_1") (pintype "passive"))
      (node (ref "C14") (pin "1") (pinfunction "1_1") (pintype "passive"))
      (node (ref "R92") (pin "1") (pinfunction "1_1") (pintype "passive"))
      (node (ref "U3") (pin "11") (pinfunction "REFSEL_11") (pintype "passive"))
      (node (ref "U3") (pin "12") (pinfunction "GND_12") (pintype "passive"))
      (node (ref "U3") (pin "4") (pinfunction "IDLSEL_4") (pintype "passive"))
      (node (ref "U3") (pin "6") (pinfunction "GND_6") (pintype "passive"))
    )
    (net (code "25") (name "GND") (class "Default")
      (node (ref "C1") (pin "1") (pinfunction "1_1") (pintype "passive"))
      (node (ref "C10") (pin "1") (pinfunction "1_1") (pintype "passive"))
      (node (ref "C11") (pin "1") (pinfunction "1_1") (pintype "passive"))
      (node (ref "C15") (pin "2") (pinfunction "-_2") (pintype "passive"))
      (node (ref "C16") (pin "1") (pinfunction "1_1") (pintype "passive"))
      (node (ref "C17") (pin "1") (pinfunction "1_1") (pintype "passive"))
      (node (ref "C18") (pin "1") (pinfunction "1_1") (pintype "passive"))
      (node (ref "C19") (pin "1") (pinfunction "1_1") (pintype "passive"))
      (node (ref "C2") (pin "1") (pinfunction "1_1") (pintype "passive"))
      (node (ref "C20") (pin "1") (pinfunction "1_1") (pintype "passive"))
      (node (ref "C23") (pin "1") (pinfunction "1_1") (pintype "passive"))
      (node (ref "C24") (pin "1") (pinfunction "1_1") (pintype "passive"))
      (node (ref "C25") (pin "1") (pinfunction "1_1") (pintype "passive"))
      (node (ref "C26") (pin "1") (pinfunction "1_1") (pintype "passive"))
      (node (ref "C27") (pin "2") (pinfunction "N_2") (pintype "passive"))
      (node (ref "C4") (pin "2") (pinfunction "-_2") (pintype "passive"))
      (node (ref "C5") (pin "1") (pinfunction "1_1") (pintype "passive"))
      (node (ref "C6") (pin "1") (pinfunction "1_1") (pintype "passive"))
      (node (ref "C7") (pin "1") (pinfunction "1_1") (pintype "passive"))
      (node (ref "C8") (pin "1") (pinfunction "1_1") (pintype "passive"))
      (node (ref "C9") (pin "1") (pinfunction "1_1") (pintype "passive"))
      (node (ref "Copt1") (pin "1") (pinfunction "1_1") (pintype "passive"))
      (node (ref "D10") (pin "2") (pinfunction "+_2") (pintype "passive"))
      (node (ref "D11") (pin "2") (pinfunction "+_2") (pintype "passive"))
      (node (ref "D2") (pin "2") (pinfunction "+_2") (pintype "passive"))
      (node (ref "D4") (pin "2") (pinfunction "+_2") (pintype "passive"))
      (node (ref "D6") (pin "2") (pinfunction "+_2") (pintype "passive"))
      (node (ref "H1") (pin "5") (pinfunction "5_5") (pintype "passive"))
      (node (ref "H3") (pin "10") (pinfunction "10_10") (pintype "passive"))
      (node (ref "H3") (pin "11") (pinfunction "11_11") (pintype "passive"))
      (node (ref "H3") (pin "12") (pinfunction "12_12") (pintype "passive"))
      (node (ref "H3") (pin "6") (pinfunction "6_6") (pintype "passive"))
      (node (ref "H3") (pin "8") (pinfunction "8_8") (pintype "passive"))
      (node (ref "IC1") (pin "7") (pinfunction "GND_7") (pintype "passive"))
      (node (ref "IC2") (pin "7") (pinfunction "GND_7") (pintype "passive"))
      (node (ref "LED8") (pin "1") (pinfunction "1_1") (pintype "passive"))
      (node (ref "LED9") (pin "1") (pinfunction "1_1") (pintype "passive"))
      (node (ref "M1") (pin "2") (pinfunction "56_2") (pintype "passive"))
      (node (ref "M2") (pin "2") (pinfunction "56_2") (pintype "passive"))
      (node (ref "M3") (pin "2") (pinfunction "56_2") (pintype "passive"))
      (node (ref "OP1") (pin "12") (pinfunction "GND_12") (pintype "passive"))
      (node (ref "OP2") (pin "12") (pinfunction "GND_12") (pintype "passive"))
      (node (ref "OP3") (pin "12") (pinfunction "GND_12") (pintype "passive"))
      (node (ref "OP4") (pin "12") (pinfunction "GND_12") (pintype "passive"))
      (node (ref "R100") (pin "1") (pinfunction "1_1") (pintype "passive"))
      (node (ref "R12") (pin "3") (pinfunction "3_3") (pintype "passive"))
      (node (ref "R22") (pin "3") (pinfunction "3_3") (pintype "passive"))
      (node (ref "R27") (pin "3") (pinfunction "3_3") (pintype "passive"))
      (node (ref "R31") (pin "3") (pinfunction "3_3") (pintype "passive"))
      (node (ref "R37") (pin "3") (pinfunction "3_3") (pintype "passive"))
      (node (ref "R39") (pin "1") (pinfunction "22_1") (pintype "passive"))
      (node (ref "R43") (pin "1") (pinfunction "1_1") (pintype "passive"))
      (node (ref "R47") (pin "1") (pinfunction "1_1") (pintype "passive"))
      (node (ref "R48") (pin "1") (pinfunction "1_1") (pintype "passive"))
      (node (ref "R5") (pin "3") (pinfunction "3_3") (pintype "passive"))
      (node (ref "R50") (pin "1") (pinfunction "1_1") (pintype "passive"))
      (node (ref "R51") (pin "3") (pinfunction "3_3") (pintype "passive"))
      (node (ref "R55") (pin "3") (pinfunction "3_3") (pintype "passive"))
      (node (ref "R58") (pin "1") (pinfunction "1_1") (pintype "passive"))
      (node (ref "R61") (pin "1") (pinfunction "83_1") (pintype "passive"))
      (node (ref "R62") (pin "3") (pinfunction "3_3") (pintype "passive"))
      (node (ref "R65") (pin "2") (pinfunction "2_2") (pintype "passive"))
      (node (ref "R68") (pin "1") (pinfunction "83_1") (pintype "passive"))
      (node (ref "R69") (pin "3") (pinfunction "3_3") (pintype "passive"))
      (node (ref "R72") (pin "2") (pinfunction "2_2") (pintype "passive"))
      (node (ref "R75") (pin "1") (pinfunction "83_1") (pintype "passive"))
      (node (ref "R76") (pin "3") (pinfunction "3_3") (pintype "passive"))
      (node (ref "R79") (pin "2") (pinfunction "2_2") (pintype "passive"))
      (node (ref "R84") (pin "1") (pinfunction "1_1") (pintype "passive"))
      (node (ref "R85") (pin "1") (pinfunction "1_1") (pintype "passive"))
      (node (ref "R87") (pin "1") (pinfunction "1_1") (pintype "passive"))
      (node (ref "R88") (pin "1") (pinfunction "1_1") (pintype "passive"))
      (node (ref "R90") (pin "1") (pinfunction "1_1") (pintype "passive"))
      (node (ref "R92") (pin "2") (pinfunction "2_2") (pintype "passive"))
      (node (ref "R96") (pin "1") (pinfunction "1_1") (pintype "passive"))
      (node (ref "R98") (pin "1") (pinfunction "1_1") (pintype "passive"))
      (node (ref "U1") (pin "7") (pinfunction "VSS_7") (pintype "passive"))
      (node (ref "U2") (pin "2") (pinfunction "GND_2") (pintype "passive"))
      (node (ref "U4") (pin "7") (pinfunction "Vss_7") (pintype "passive"))
      (node (ref "U5") (pin "3") (pinfunction "GND_2_3") (pintype "passive"))
      (node (ref "U5") (pin "6") (pinfunction "GND_6") (pintype "passive"))
      (node (ref "U5") (pin "7") (pinfunction "PG_7") (pintype "output"))
      (node (ref "U5") (pin "9") (pinfunction "EP_9") (pintype "passive"))
      (node (ref "U6") (pin "1") (pinfunction "Gnd_1") (pintype "passive"))
      (node (ref "U6") (pin "10") (pinfunction "Gnd_10") (pintype "passive"))
      (node (ref "U6") (pin "11") (pinfunction "Gnd_11") (pintype "passive"))
      (node (ref "U6") (pin "12") (pinfunction "Gnd_12") (pintype "passive"))
      (node (ref "U6") (pin "13") (pinfunction "Gnd_13") (pintype "passive"))
      (node (ref "U6") (pin "14") (pinfunction "Gnd_14") (pintype "passive"))
      (node (ref "U6") (pin "15") (pinfunction "Gnd_15") (pintype "passive"))
      (node (ref "U6") (pin "16") (pinfunction "Gnd_16") (pintype "passive"))
      (node (ref "U6") (pin "17") (pinfunction "Gnd_17") (pintype "passive"))
      (node (ref "U6") (pin "9") (pinfunction "Gnd_9") (pintype "passive"))
    )
    (net (code "26") (name "Net-(C3--)") (class "Default")
      (node (ref "C3") (pin "2") (pinfunction "-_2") (pintype "passive"))
      (node (ref "IC1") (pin "12") (pinfunction "in_12") (pintype "passive"))
      (node (ref "R19") (pin "2") (pinfunction "2_2") (pintype "passive"))
    )
    (net (code "27") (name "Net-(C4-+)") (class "Default")
      (node (ref "C4") (pin "1") (pinfunction "+_1") (pintype "passive"))
      (node (ref "OP2") (pin "8") (pinfunction "-_8") (pintype "passive"))
      (node (ref "R30") (pin "2") (pinfunction "2_2") (pintype "passive"))
    )
    (net (code "28") (name "Net-(C15-+)") (class "Default")
      (node (ref "C15") (pin "1") (pinfunction "+_1") (pintype "passive"))
      (node (ref "R52") (pin "2") (pinfunction "2_2") (pintype "passive"))
      (node (ref "U1") (pin "13") (pinfunction "D_13") (pintype "passive"))
    )
    (net (code "29") (name "Net-(D5-+)") (class "Default")
      (node (ref "C8") (pin "2") (pinfunction "2_2") (pintype "passive"))
      (node (ref "D5") (pin "2") (pinfunction "+_2") (pintype "passive"))
      (node (ref "D6") (pin "1") (pinfunction "-_1") (pintype "passive"))
      (node (ref "R40") (pin "2") (pinfunction "2_2") (pintype "passive"))
      (node (ref "R41") (pin "1") (pinfunction "1_1") (pintype "passive"))
    )
    (net (code "30") (name "Net-(D7-70)") (class "Default")
      (node (ref "D7") (pin "2") (pinfunction "70_2") (pintype "passive"))
      (node (ref "O1") (pin "4") (pinfunction "6_4") (pintype "passive"))
      (node (ref "R97") (pin "1") (pinfunction "1_1") (pintype "passive"))
      (node (ref "re1") (pin "1") (pinfunction "122_1") (pintype "passive"))
      (node (ref "re1") (pin "3") (pinfunction "119_3") (pintype "passive"))
    )
    (net (code "31") (name "Net-(D8-70)") (class "Default")
      (node (ref "D8") (pin "2") (pinfunction "70_2") (pintype "passive"))
      (node (ref "O2") (pin "4") (pinfunction "6_4") (pintype "passive"))
      (node (ref "R99") (pin "2") (pinfunction "2_2") (pintype "passive"))
      (node (ref "re2") (pin "1") (pinfunction "122_1") (pintype "passive"))
      (node (ref "re2") (pin "3") (pinfunction "119_3") (pintype "passive"))
    )
    (net (code "32") (name "Net-(D9-70)") (class "Default")
      (node (ref "D9") (pin "2") (pinfunction "70_2") (pintype "passive"))
      (node (ref "O3") (pin "4") (pinfunction "6_4") (pintype "passive"))
      (node (ref "R95") (pin "2") (pinfunction "2_2") (pintype "passive"))
      (node (ref "re3") (pin "1") (pinfunction "122_1") (pintype "passive"))
      (node (ref "re3") (pin "3") (pinfunction "119_3") (pintype "passive"))
    )
    (net (code "33") (name "Net-(D11--)") (class "Default")
      (node (ref "C24") (pin "2") (pinfunction "2_2") (pintype "passive"))
      (node (ref "D11") (pin "1") (pinfunction "-_1") (pintype "passive"))
      (node (ref "H3") (pin "7") (pinfunction "7_7") (pintype "passive"))
      (node (ref "U6") (pin "5") (pinfunction "Out_5") (pintype "passive"))
    )
    (net (code "34") (name "Net-(D12-+)") (class "Default")
      (node (ref "D12") (pin "2") (pinfunction "+_2") (pintype "passive"))
      (node (ref "H3") (pin "4") (pinfunction "4_4") (pintype "passive"))
    )
    (net (code "35") (name "Net-(D12--)") (class "Default")
      (node (ref "D12") (pin "1") (pinfunction "-_1") (pintype "passive"))
      (node (ref "D13") (pin "1") (pinfunction "-_1") (pintype "passive"))
      (node (ref "R90") (pin "2") (pinfunction "2_2") (pintype "passive"))
      (node (ref "U6") (pin "3") (pinfunction "EN_3") (pintype "passive"))
    )
    (net (code "36") (name "Net-(D13-+)") (class "Default")
      (node (ref "D13") (pin "2") (pinfunction "+_2") (pintype "passive"))
      (node (ref "OP3") (pin "13") (pinfunction "out_13") (pintype "passive"))
      (node (ref "R54") (pin "1") (pinfunction "1_1") (pintype "passive"))
      (node (ref "R56") (pin "2") (pinfunction "2_2") (pintype "passive"))
    )
    (net (code "37") (name "Net-(H1-Pad6)") (class "Default")
      (node (ref "H1") (pin "6") (pinfunction "6_6") (pintype "passive"))
      (node (ref "H1") (pin "8") (pinfunction "8_8") (pintype "passive"))
      (node (ref "R91") (pin "2") (pinfunction "2_2") (pintype "passive"))
    )
    (net (code "38") (name "Net-(H1-Pad7)") (class "Default")
      (node (ref "H1") (pin "7") (pinfunction "7_7") (pintype "passive"))
      (node (ref "H1") (pin "9") (pinfunction "9_9") (pintype "passive"))
    )
    (net (code "39") (name "Net-(H1-Pad10)") (class "Default")
      (node (ref "H1") (pin "10") (pinfunction "10_10") (pintype "passive"))
      (node (ref "H1") (pin "12") (pinfunction "12_12") (pintype "passive"))
    )
    (net (code "40") (name "Net-(H1-Pad11)") (class "Default")
      (node (ref "H1") (pin "11") (pinfunction "11_11") (pintype "passive"))
      (node (ref "H1") (pin "13") (pinfunction "13_13") (pintype "passive"))
    )
    (net (code "41") (name "Net-(H1-Pad14)") (class "Default")
      (node (ref "H1") (pin "14") (pinfunction "14_14") (pintype "passive"))
      (node (ref "H1") (pin "16") (pinfunction "16_16") (pintype "passive"))
    )
    (net (code "42") (name "Net-(H1-Pad15)") (class "Default")
      (node (ref "H1") (pin "15") (pinfunction "15_15") (pintype "passive"))
      (node (ref "H1") (pin "17") (pinfunction "17_17") (pintype "passive"))
    )
    (net (code "43") (name "Net-(H1-Pad18)") (class "Default")
      (node (ref "H1") (pin "18") (pinfunction "18_18") (pintype "passive"))
      (node (ref "H1") (pin "19") (pinfunction "19_19") (pintype "passive"))
    )
    (net (code "44") (name "Net-(IC1A-out)") (class "Default")
      (node (ref "IC1") (pin "3") (pinfunction "out_3") (pintype "passive"))
      (node (ref "R19") (pin "1") (pinfunction "1_1") (pintype "passive"))
    )
    (net (code "45") (name "Net-(IC1B-in-Pad6)") (class "Default")
      (node (ref "IC1") (pin "6") (pinfunction "in_6") (pintype "passive"))
      (node (ref "R16") (pin "1") (pinfunction "1_1") (pintype "passive"))
      (node (ref "SW1") (pin "3") (pinfunction "3_3") (pintype "passive"))
    )
    (net (code "46") (name "Net-(IC1B-out)") (class "Default")
      (node (ref "IC1") (pin "4") (pinfunction "out_4") (pintype "passive"))
      (node (ref "R16") (pin "2") (pinfunction "2_2") (pintype "passive"))
      (node (ref "U1") (pin "3") (pinfunction "A_3") (pintype "passive"))
    )
    (net (code "47") (name "Net-(IC1C-in-Pad9)") (class "Default")
      (node (ref "IC1") (pin "9") (pinfunction "in_9") (pintype "passive"))
      (node (ref "R18") (pin "1") (pinfunction "1_1") (pintype "passive"))
      (node (ref "SW2") (pin "3") (pinfunction "3_3") (pintype "passive"))
    )
    (net (code "48") (name "Net-(IC1C-out)") (class "Default")
      (node (ref "IC1") (pin "10") (pinfunction "out_10") (pintype "passive"))
      (node (ref "R18") (pin "2") (pinfunction "2_2") (pintype "passive"))
      (node (ref "U1") (pin "6") (pinfunction "B_6") (pintype "passive"))
    )
    (net (code "49") (name "Net-(IC1D-out)") (class "Default")
      (node (ref "IC1") (pin "11") (pinfunction "out_11") (pintype "passive"))
      (node (ref "IC2") (pin "8") (pinfunction "in_8") (pintype "passive"))
    )
    (net (code "50") (name "Net-(IC2A-out)") (class "Default")
      (node (ref "IC2") (pin "3") (pinfunction "out_3") (pintype "passive"))
      (node (ref "R52") (pin "1") (pinfunction "1_1") (pintype "passive"))
    )
    (net (code "51") (name "Net-(IC2B-out)") (class "Default")
      (node (ref "IC2") (pin "4") (pinfunction "out_4") (pintype "passive"))
      (node (ref "R30") (pin "1") (pinfunction "1_1") (pintype "passive"))
    )
    (net (code "52") (name "Net-(IC2C-in-Pad9)") (class "Default")
      (node (ref "IC2") (pin "9") (pinfunction "in_9") (pintype "passive"))
      (node (ref "U1") (pin "12") (pinfunction "12_12") (pintype "passive"))
    )
    (net (code "53") (name "Net-(IC2D-in-Pad13)") (class "Default")
      (node (ref "IC2") (pin "13") (pinfunction "in_13") (pintype "passive"))
      (node (ref "R33") (pin "1") (pinfunction "1_1") (pintype "passive"))
      (node (ref "SW3") (pin "3") (pinfunction "3_3") (pintype "passive"))
    )
    (net (code "54") (name "Net-(IC2D-out)") (class "Default")
      (node (ref "IC2") (pin "11") (pinfunction "out_11") (pintype "passive"))
      (node (ref "R33") (pin "2") (pinfunction "2_2") (pintype "passive"))
      (node (ref "U1") (pin "10") (pinfunction "C_10") (pintype "passive"))
    )
    (net (code "55") (name "Net-(LED1-Pad2)") (class "Default")
      (node (ref "LED1") (pin "2") (pinfunction "2_2") (pintype "passive"))
      (node (ref "R101") (pin "1") (pinfunction "1_1") (pintype "passive"))
    )
    (net (code "56") (name "Net-(LED2-Pad1)") (class "Default")
      (node (ref "LED2") (pin "1") (pinfunction "1_1") (pintype "passive"))
      (node (ref "R86") (pin "2") (pinfunction "2_2") (pintype "passive"))
    )
    (net (code "57") (name "Net-(LED3-Pad1)") (class "Default")
      (node (ref "LED3") (pin "1") (pinfunction "1_1") (pintype "passive"))
      (node (ref "U1") (pin "1") (pinfunction "1_1") (pintype "passive"))
    )
    (net (code "58") (name "Net-(LED3-Pad2)") (class "Default")
      (node (ref "LED3") (pin "2") (pinfunction "2_2") (pintype "passive"))
      (node (ref "R15") (pin "1") (pinfunction "1_1") (pintype "passive"))
    )
    (net (code "59") (name "Net-(LED4-Pad1)") (class "Default")
      (node (ref "LED4") (pin "1") (pinfunction "1_1") (pintype "passive"))
      (node (ref "U1") (pin "4") (pinfunction "4_4") (pintype "passive"))
    )
    (net (code "60") (name "Net-(LED4-Pad2)") (class "Default")
      (node (ref "LED4") (pin "2") (pinfunction "2_2") (pintype "passive"))
      (node (ref "R17") (pin "1") (pinfunction "1_1") (pintype "passive"))
    )
    (net (code "61") (name "Net-(LED5-Pad1)") (class "Default")
      (node (ref "LED5") (pin "1") (pinfunction "1_1") (pintype "passive"))
      (node (ref "U1") (pin "8") (pinfunction "8_8") (pintype "passive"))
    )
    (net (code "62") (name "Net-(LED5-Pad2)") (class "Default")
      (node (ref "LED5") (pin "2") (pinfunction "2_2") (pintype "passive"))
      (node (ref "R34") (pin "1") (pinfunction "1_1") (pintype "passive"))
    )
    (net (code "63") (name "Net-(LED6-Pad2)") (class "Default")
      (node (ref "LED6") (pin "2") (pinfunction "2_2") (pintype "passive"))
      (node (ref "R6") (pin "1") (pinfunction "1_1") (pintype "passive"))
    )
    (net (code "64") (name "Net-(LED7-Pad2)") (class "Default")
      (node (ref "LED7") (pin "2") (pinfunction "2_2") (pintype "passive"))
      (node (ref "R13") (pin "1") (pinfunction "1_1") (pintype "passive"))
    )
    (net (code "65") (name "Net-(LED8-Pad2)") (class "Default")
      (node (ref "LED8") (pin "2") (pinfunction "2_2") (pintype "passive"))
      (node (ref "R89") (pin "1") (pinfunction "1_1") (pintype "passive"))
    )
    (net (code "66") (name "Net-(LED9-Pad2)") (class "Default")
      (node (ref "LED9") (pin "2") (pinfunction "2_2") (pintype "passive"))
      (node (ref "R91") (pin "1") (pinfunction "1_1") (pintype "passive"))
    )
    (net (code "67") (name "Net-(M1-54)") (class "Default")
      (node (ref "M1") (pin "1") (pinfunction "54_1") (pintype "passive"))
      (node (ref "R64") (pin "2") (pinfunction "2_2") (pintype "passive"))
      (node (ref "R65") (pin "1") (pinfunction "1_1") (pintype "passive"))
    )
    (net (code "68") (name "Net-(M1-55)") (class "Default")
      (node (ref "M1") (pin "3") (pinfunction "55_3") (pintype "passive"))
      (node (ref "O1") (pin "3") (pinfunction "9_3") (pintype "passive"))
      (node (ref "re1") (pin "4") (pinfunction "120_4") (pintype "passive"))
    )
    (net (code "69") (name "Net-(M2-54)") (class "Default")
      (node (ref "M2") (pin "1") (pinfunction "54_1") (pintype "passive"))
      (node (ref "R71") (pin "2") (pinfunction "2_2") (pintype "passive"))
      (node (ref "R72") (pin "1") (pinfunction "1_1") (pintype "passive"))
    )
    (net (code "70") (name "Net-(M2-55)") (class "Default")
      (node (ref "M2") (pin "3") (pinfunction "55_3") (pintype "passive"))
      (node (ref "O2") (pin "3") (pinfunction "9_3") (pintype "passive"))
      (node (ref "re2") (pin "4") (pinfunction "120_4") (pintype "passive"))
    )
    (net (code "71") (name "Net-(M3-54)") (class "Default")
      (node (ref "M3") (pin "1") (pinfunction "54_1") (pintype "passive"))
      (node (ref "R78") (pin "2") (pinfunction "2_2") (pintype "passive"))
      (node (ref "R79") (pin "1") (pinfunction "1_1") (pintype "passive"))
    )
    (net (code "72") (name "Net-(M3-55)") (class "Default")
      (node (ref "M3") (pin "3") (pinfunction "55_3") (pintype "passive"))
      (node (ref "O3") (pin "3") (pinfunction "9_3") (pintype "passive"))
      (node (ref "re3") (pin "4") (pinfunction "120_4") (pintype "passive"))
    )
    (net (code "73") (name "Net-(O1-5)") (class "Default")
      (node (ref "H1") (pin "3") (pinfunction "3_3") (pintype "passive"))
      (node (ref "O1") (pin "2") (pinfunction "5_2") (pintype "passive"))
    )
    (net (code "74") (name "Net-(O1-7)") (class "Default")
      (node (ref "O1") (pin "1") (pinfunction "7_1") (pintype "passive"))
      (node (ref "R59") (pin "1") (pinfunction "83_1") (pintype "passive"))
    )
    (net (code "75") (name "Net-(O2-5)") (class "Default")
      (node (ref "H1") (pin "2") (pinfunction "2_2") (pintype "passive"))
      (node (ref "O2") (pin "2") (pinfunction "5_2") (pintype "passive"))
    )
    (net (code "76") (name "Net-(O2-7)") (class "Default")
      (node (ref "O2") (pin "1") (pinfunction "7_1") (pintype "passive"))
      (node (ref "R66") (pin "1") (pinfunction "83_1") (pintype "passive"))
    )
    (net (code "77") (name "Net-(O3-5)") (class "Default")
      (node (ref "H1") (pin "1") (pinfunction "1_1") (pintype "passive"))
      (node (ref "O3") (pin "2") (pinfunction "5_2") (pintype "passive"))
    )
    (net (code "78") (name "Net-(O3-7)") (class "Default")
      (node (ref "O3") (pin "1") (pinfunction "7_1") (pintype "passive"))
      (node (ref "R73") (pin "1") (pinfunction "83_1") (pintype "passive"))
    )
    (net (code "79") (name "Net-(OP1C-out)") (class "Default")
      (node (ref "IC1") (pin "2") (pinfunction "in_2") (pintype "passive"))
      (node (ref "IC1") (pin "8") (pinfunction "in_8") (pintype "passive"))
      (node (ref "LED7") (pin "1") (pinfunction "1_1") (pintype "passive"))
      (node (ref "OP1") (pin "13") (pinfunction "out_13") (pintype "passive"))
      (node (ref "OP1") (pin "14") (pinfunction "out_14") (pintype "passive"))
      (node (ref "R14") (pin "1") (pinfunction "1_1") (pintype "passive"))
    )
    (net (code "80") (name "Net-(OP2A-+)") (class "Default")
      (node (ref "OP2") (pin "5") (pinfunction "+_5") (pintype "passive"))
      (node (ref "R26") (pin "2") (pinfunction "84_2") (pintype "passive"))
      (node (ref "R28") (pin "1") (pinfunction "83_1") (pintype "passive"))
    )
    (net (code "81") (name "Net-(OP2A-out)") (class "Default")
      (node (ref "IC2") (pin "6") (pinfunction "in_6") (pintype "passive"))
      (node (ref "OP2") (pin "2") (pinfunction "out_2") (pintype "passive"))
      (node (ref "R28") (pin "2") (pinfunction "84_2") (pintype "passive"))
      (node (ref "R29") (pin "1") (pinfunction "1_1") (pintype "passive"))
    )
    (net (code "82") (name "Net-(OP2B-out)") (class "Default")
      (node (ref "IC2") (pin "5") (pinfunction "in_5") (pintype "passive"))
      (node (ref "OP2") (pin "1") (pinfunction "out_1") (pintype "passive"))
      (node (ref "R23") (pin "1") (pinfunction "1_1") (pintype "passive"))
    )
    (net (code "83") (name "Net-(OP2C-+)") (class "Default")
      (node (ref "OP2") (pin "9") (pinfunction "+_9") (pintype "passive"))
      (node (ref "R31") (pin "2") (pinfunction "2_2") (pintype "passive"))
    )
    (net (code "84") (name "Net-(OP2C-out)") (class "Default")
      (node (ref "IC1") (pin "13") (pinfunction "in_13") (pintype "passive"))
      (node (ref "IC2") (pin "12") (pinfunction "in_12") (pintype "passive"))
      (node (ref "OP2") (pin "14") (pinfunction "out_14") (pintype "passive"))
      (node (ref "R32") (pin "1") (pinfunction "1_1") (pintype "passive"))
    )
    (net (code "85") (name "Net-(OP2D-+)") (class "Default")
      (node (ref "OP2") (pin "11") (pinfunction "+_11") (pintype "passive"))
      (node (ref "R35") (pin "2") (pinfunction "84_2") (pintype "passive"))
      (node (ref "R36") (pin "1") (pinfunction "83_1") (pintype "passive"))
    )
    (net (code "86") (name "Net-(OP2D--)") (class "Default")
      (node (ref "OP2") (pin "10") (pinfunction "-_10") (pintype "passive"))
      (node (ref "R37") (pin "2") (pinfunction "2_2") (pintype "passive"))
    )
    (net (code "87") (name "Net-(OP2D-out)") (class "Default")
      (node (ref "IC2") (pin "1") (pinfunction "in_1") (pintype "passive"))
      (node (ref "OP2") (pin "13") (pinfunction "out_13") (pintype "passive"))
      (node (ref "R36") (pin "2") (pinfunction "84_2") (pintype "passive"))
      (node (ref "R38") (pin "1") (pinfunction "1_1") (pintype "passive"))
    )
    (net (code "88") (name "Net-(OP3A-+)") (class "Default")
      (node (ref "OP3") (pin "5") (pinfunction "+_5") (pintype "passive"))
      (node (ref "U3") (pin "2") (pinfunction "VoA_2") (pintype "passive"))
    )
    (net (code "89") (name "Net-(OP3A--)") (class "Default")
      (node (ref "OP3") (pin "4") (pinfunction "-_4") (pintype "passive"))
      (node (ref "R51") (pin "2") (pinfunction "2_2") (pintype "passive"))
    )
    (net (code "90") (name "Net-(OP3B-+)") (class "Default")
      (node (ref "OP3") (pin "7") (pinfunction "+_7") (pintype "passive"))
      (node (ref "R42") (pin "1") (pinfunction "1_1") (pintype "passive"))
      (node (ref "R43") (pin "2") (pinfunction "2_2") (pintype "passive"))
      (node (ref "R45") (pin "2") (pinfunction "2_2") (pintype "passive"))
    )
    (net (code "91") (name "Net-(OP3B--)") (class "Default")
      (node (ref "OP3") (pin "6") (pinfunction "-_6") (pintype "passive"))
      (node (ref "R41") (pin "2") (pinfunction "2_2") (pintype "passive"))
    )
    (net (code "92") (name "Net-(OP3B-out)") (class "Default")
      (node (ref "OP3") (pin "1") (pinfunction "out_1") (pintype "passive"))
      (node (ref "OP3") (pin "9") (pinfunction "+_9") (pintype "passive"))
      (node (ref "R44") (pin "1") (pinfunction "1_1") (pintype "passive"))
      (node (ref "R46") (pin "2") (pinfunction "2_2") (pintype "passive"))
      (node (ref "U2") (pin "1") (pinfunction "TRIG_1") (pintype "passive"))
    )
    (net (code "93") (name "Net-(OP3C--)") (class "Default")
      (node (ref "OP3") (pin "8") (pinfunction "-_8") (pintype "passive"))
      (node (ref "R57") (pin "1") (pinfunction "1_1") (pintype "passive"))
      (node (ref "R58") (pin "2") (pinfunction "2_2") (pintype "passive"))
    )
    (net (code "94") (name "Net-(OP3C-out)") (class "Default")
      (node (ref "H3") (pin "9") (pinfunction "9_9") (pintype "passive"))
      (node (ref "LED1") (pin "1") (pinfunction "1_1") (pintype "passive"))
      (node (ref "OP3") (pin "14") (pinfunction "out_14") (pintype "passive"))
      (node (ref "R94") (pin "1") (pinfunction "1_1") (pintype "passive"))
    )
    (net (code "95") (name "Net-(OP3D-+)") (class "Default")
      (node (ref "OP3") (pin "11") (pinfunction "+_11") (pintype "passive"))
      (node (ref "R53") (pin "1") (pinfunction "1_1") (pintype "passive"))
      (node (ref "R54") (pin "2") (pinfunction "2_2") (pintype "passive"))
    )
    (net (code "96") (name "Net-(OP3D--)") (class "Default")
      (node (ref "OP3") (pin "10") (pinfunction "-_10") (pintype "passive"))
      (node (ref "R55") (pin "2") (pinfunction "2_2") (pintype "passive"))
    )
    (net (code "97") (name "Net-(OP4A-+)") (class "Default")
      (node (ref "OP4") (pin "5") (pinfunction "+_5") (pintype "passive"))
      (node (ref "R67") (pin "2") (pinfunction "84_2") (pintype "passive"))
      (node (ref "R68") (pin "2") (pinfunction "84_2") (pintype "passive"))
    )
    (net (code "98") (name "Net-(OP4A--)") (class "Default")
      (node (ref "OP4") (pin "4") (pinfunction "-_4") (pintype "passive"))
      (node (ref "R69") (pin "2") (pinfunction "2_2") (pintype "passive"))
    )
    (net (code "99") (name "Net-(OP4A-out)") (class "Default")
      (node (ref "OP4") (pin "2") (pinfunction "out_2") (pintype "passive"))
      (node (ref "R70") (pin "1") (pinfunction "1_1") (pintype "passive"))
      (node (ref "R71") (pin "1") (pinfunction "1_1") (pintype "passive"))
    )
    (net (code "100") (name "Net-(OP4B-+)") (class "Default")
      (node (ref "OP4") (pin "7") (pinfunction "+_7") (pintype "passive"))
      (node (ref "R60") (pin "2") (pinfunction "84_2") (pintype "passive"))
      (node (ref "R61") (pin "2") (pinfunction "84_2") (pintype "passive"))
    )
    (net (code "101") (name "Net-(OP4B--)") (class "Default")
      (node (ref "OP4") (pin "6") (pinfunction "-_6") (pintype "passive"))
      (node (ref "R62") (pin "2") (pinfunction "2_2") (pintype "passive"))
    )
    (net (code "102") (name "Net-(OP4B-out)") (class "Default")
      (node (ref "OP4") (pin "1") (pinfunction "out_1") (pintype "passive"))
      (node (ref "R63") (pin "1") (pinfunction "1_1") (pintype "passive"))
      (node (ref "R64") (pin "1") (pinfunction "1_1") (pintype "passive"))
    )
    (net (code "103") (name "Net-(OP4C-+)") (class "Default")
      (node (ref "OP4") (pin "9") (pinfunction "+_9") (pintype "passive"))
      (node (ref "R87") (pin "2") (pinfunction "2_2") (pintype "passive"))
    )
    (net (code "104") (name "Net-(OP4C--)") (class "Default")
      (node (ref "OP4") (pin "8") (pinfunction "-_8") (pintype "passive"))
      (node (ref "R88") (pin "2") (pinfunction "2_2") (pintype "passive"))
    )
    (net (code "105") (name "Net-(OP4D-+)") (class "Default")
      (node (ref "OP4") (pin "11") (pinfunction "+_11") (pintype "passive"))
      (node (ref "R74") (pin "2") (pinfunction "84_2") (pintype "passive"))
      (node (ref "R75") (pin "2") (pinfunction "84_2") (pintype "passive"))
    )
    (net (code "106") (name "Net-(OP4D--)") (class "Default")
      (node (ref "OP4") (pin "10") (pinfunction "-_10") (pintype "passive"))
      (node (ref "R76") (pin "2") (pinfunction "2_2") (pintype "passive"))
    )
    (net (code "107") (name "Net-(OP4D-out)") (class "Default")
      (node (ref "OP4") (pin "13") (pinfunction "out_13") (pintype "passive"))
      (node (ref "R77") (pin "1") (pinfunction "1_1") (pintype "passive"))
      (node (ref "R78") (pin "1") (pinfunction "1_1") (pintype "passive"))
    )
    (net (code "108") (name "Net-(R4-Pad3)") (class "Default")
      (node (ref "R4") (pin "3") (pinfunction "3_3") (pintype "passive"))
      (node (ref "R5") (pin "1") (pinfunction "1_1") (pintype "passive"))
    )
    (net (code "109") (name "Net-(R11-Pad3)") (class "Default")
      (node (ref "R11") (pin "3") (pinfunction "3_3") (pintype "passive"))
      (node (ref "R12") (pin "1") (pinfunction "1_1") (pintype "passive"))
    )
    (net (code "110") (name "Net-(R39-24)") (class "Default")
      (node (ref "C7") (pin "2") (pinfunction "2_2") (pintype "passive"))
      (node (ref "H2") (pin "8") (pinfunction "8_8") (pintype "passive"))
      (node (ref "R39") (pin "2") (pinfunction "24_2") (pintype "passive"))
      (node (ref "R40") (pin "1") (pinfunction "1_1") (pintype "passive"))
    )
    (net (code "111") (name "Net-(R45-Pad1)") (class "Default")
      (node (ref "R45") (pin "1") (pinfunction "1_1") (pintype "passive"))
      (node (ref "R46") (pin "1") (pinfunction "1_1") (pintype "passive"))
      (node (ref "R47") (pin "2") (pinfunction "2_2") (pintype "passive"))
    )
    (net (code "112") (name "Net-(R67-83)") (class "Default")
      (node (ref "H2") (pin "5") (pinfunction "5_5") (pintype "passive"))
      (node (ref "R67") (pin "1") (pinfunction "83_1") (pintype "passive"))
    )
    (net (code "113") (name "Net-(R74-83)") (class "Default")
      (node (ref "H2") (pin "4") (pinfunction "4_4") (pintype "passive"))
      (node (ref "R74") (pin "1") (pinfunction "83_1") (pintype "passive"))
    )
    (net (code "114") (name "Net-(R80-83)") (class "Default")
      (node (ref "H2") (pin "1") (pinfunction "1_1") (pintype "passive"))
      (node (ref "R80") (pin "1") (pinfunction "83_1") (pintype "passive"))
    )
    (net (code "115") (name "Net-(R80-84)") (class "Default")
      (node (ref "R80") (pin "2") (pinfunction "84_2") (pintype "passive"))
      (node (ref "U4") (pin "1") (pinfunction "1X_1") (pintype "passive"))
    )
    (net (code "116") (name "Net-(R81-83)") (class "Default")
      (node (ref "H2") (pin "2") (pinfunction "2_2") (pintype "passive"))
      (node (ref "R81") (pin "1") (pinfunction "83_1") (pintype "passive"))
    )
    (net (code "117") (name "Net-(R81-84)") (class "Default")
      (node (ref "R81") (pin "2") (pinfunction "84_2") (pintype "passive"))
      (node (ref "U4") (pin "4") (pinfunction "2X_4") (pintype "passive"))
    )
    (net (code "118") (name "Net-(R82-83)") (class "Default")
      (node (ref "H2") (pin "3") (pinfunction "3_3") (pintype "passive"))
      (node (ref "R82") (pin "1") (pinfunction "83_1") (pintype "passive"))
    )
    (net (code "119") (name "Net-(R82-84)") (class "Default")
      (node (ref "R82") (pin "2") (pinfunction "84_2") (pintype "passive"))
      (node (ref "U4") (pin "8") (pinfunction "3X_8") (pintype "passive"))
    )
    (net (code "120") (name "Net-(U2-DIV)") (class "Default")
      (node (ref "R49") (pin "1") (pinfunction "1_1") (pintype "passive"))
      (node (ref "R50") (pin "2") (pinfunction "2_2") (pintype "passive"))
      (node (ref "U2") (pin "4") (pinfunction "DIV_4") (pintype "passive"))
    )
    (net (code "121") (name "Net-(U2-OUT)") (class "Default")
      (node (ref "U2") (pin "6") (pinfunction "OUT_6") (pintype "passive"))
      (node (ref "U3") (pin "9") (pinfunction "INA_9") (pintype "passive"))
    )
    (net (code "122") (name "Net-(U2-SET)") (class "Default")
      (node (ref "R48") (pin "2") (pinfunction "2_2") (pintype "passive"))
      (node (ref "U2") (pin "3") (pinfunction "SET_3") (pintype "passive"))
    )
    (net (code "123") (name "Net-(U4-1A)") (class "Default")
      (node (ref "R95") (pin "1") (pinfunction "1_1") (pintype "passive"))
      (node (ref "R96") (pin "2") (pinfunction "2_2") (pintype "passive"))
      (node (ref "U4") (pin "3") (pinfunction "1A_3") (pintype "passive"))
    )
    (net (code "124") (name "Net-(U4-2A)") (class "Default")
      (node (ref "R100") (pin "2") (pinfunction "2_2") (pintype "passive"))
      (node (ref "R99") (pin "1") (pinfunction "1_1") (pintype "passive"))
      (node (ref "U4") (pin "6") (pinfunction "2A_6") (pintype "passive"))
    )
    (net (code "125") (name "Net-(U4-3A)") (class "Default")
      (node (ref "R97") (pin "2") (pinfunction "2_2") (pintype "passive"))
      (node (ref "R98") (pin "2") (pinfunction "2_2") (pintype "passive"))
      (node (ref "U4") (pin "10") (pinfunction "3A_10") (pintype "passive"))
    )
    (net (code "126") (name "Net-(U6-Fault)") (class "Default")
      (node (ref "R86") (pin "1") (pinfunction "1_1") (pintype "passive"))
      (node (ref "U6") (pin "6") (pinfunction "Fault_6") (pintype "passive"))
    )
    (net (code "127") (name "Net-(U6-Ilm)") (class "Default")
      (node (ref "R85") (pin "2") (pinfunction "2_2") (pintype "passive"))
      (node (ref "U6") (pin "7") (pinfunction "Ilm_7") (pintype "passive"))
    )
    (net (code "128") (name "Net-(U6-Ovlo)") (class "Default")
      (node (ref "R83") (pin "1") (pinfunction "1_1") (pintype "passive"))
      (node (ref "R84") (pin "2") (pinfunction "2_2") (pintype "passive"))
      (node (ref "U6") (pin "8") (pinfunction "Ovlo_8") (pintype "passive"))
    )
    (net (code "129") (name "Net-(U6-dVdt)") (class "Default")
      (node (ref "Copt1") (pin "2") (pinfunction "2_2") (pintype "passive"))
      (node (ref "U6") (pin "2") (pinfunction "dVdt_2") (pintype "passive"))
    )
    (net (code "130") (name "Net-(re1-117)") (class "Default")
      (node (ref "H1") (pin "20") (pinfunction "20_20") (pintype "passive"))
      (node (ref "re1") (pin "6") (pinfunction "117_6") (pintype "passive"))
    )
    (net (code "131") (name "Net-(re1-118)") (class "Default")
      (node (ref "re1") (pin "5") (pinfunction "118_5") (pintype "passive"))
      (node (ref "re2") (pin "6") (pinfunction "117_6") (pintype "passive"))
    )
    (net (code "132") (name "Net-(re2-118)") (class "Default")
      (node (ref "re2") (pin "5") (pinfunction "118_5") (pintype "passive"))
      (node (ref "re3") (pin "6") (pinfunction "117_6") (pintype "passive"))
    )
    (net (code "133") (name "Net-(re3-118)") (class "Default")
      (node (ref "H1") (pin "4") (pinfunction "4_4") (pintype "passive"))
      (node (ref "re3") (pin "5") (pinfunction "118_5") (pintype "passive"))
    )
    (net (code "134") (name "unconnected-(OP4C-out-Pad14)") (class "Default")
      (node (ref "OP4") (pin "14") (pinfunction "out_14") (pintype "passive"))
    )
    (net (code "135") (name "unconnected-(SW1-Pad2)") (class "Default")
      (node (ref "SW1") (pin "2") (pinfunction "2_2") (pintype "passive"))
    )
    (net (code "136") (name "unconnected-(SW1-Pad4)") (class "Default")
      (node (ref "SW1") (pin "4") (pinfunction "4_4") (pintype "passive"))
    )
    (net (code "137") (name "unconnected-(SW2-Pad2)") (class "Default")
      (node (ref "SW2") (pin "2") (pinfunction "2_2") (pintype "passive"))
    )
    (net (code "138") (name "unconnected-(SW2-Pad4)") (class "Default")
      (node (ref "SW2") (pin "4") (pinfunction "4_4") (pintype "passive"))
    )
    (net (code "139") (name "unconnected-(SW3-Pad2)") (class "Default")
      (node (ref "SW3") (pin "2") (pinfunction "2_2") (pintype "passive"))
    )
    (net (code "140") (name "unconnected-(SW3-Pad4)") (class "Default")
      (node (ref "SW3") (pin "4") (pinfunction "4_4") (pintype "passive"))
    )
    (net (code "141") (name "unconnected-(U1-Pad2)") (class "Default")
      (node (ref "U1") (pin "2") (pinfunction "2_2") (pintype "passive"))
    )
    (net (code "142") (name "unconnected-(U1-Pad5)") (class "Default")
      (node (ref "U1") (pin "5") (pinfunction "5_5") (pintype "passive"))
    )
    (net (code "143") (name "unconnected-(U1-Pad9)") (class "Default")
      (node (ref "U1") (pin "9") (pinfunction "9_9") (pintype "passive"))
    )
    (net (code "144") (name "unconnected-(U1-Pad11)") (class "Default")
      (node (ref "U1") (pin "11") (pinfunction "11_11") (pintype "passive"))
    )
    (net (code "145") (name "unconnected-(U3-INB-Pad8)") (class "Default")
      (node (ref "U3") (pin "8") (pinfunction "INB_8") (pintype "passive"))
    )
    (net (code "146") (name "unconnected-(U3-VoB-Pad3)") (class "Default")
      (node (ref "U3") (pin "3") (pinfunction "VoB_3") (pintype "passive"))
    )
    (net (code "147") (name "unconnected-(U4-1Y-Pad2)") (class "Default")
      (node (ref "U4") (pin "2") (pinfunction "1Y_2") (pintype "passive"))
    )
    (net (code "148") (name "unconnected-(U4-2Y-Pad5)") (class "Default")
      (node (ref "U4") (pin "5") (pinfunction "2Y_5") (pintype "passive"))
    )
    (net (code "149") (name "unconnected-(U4-3Y-Pad9)") (class "Default")
      (node (ref "U4") (pin "9") (pinfunction "3Y_9") (pintype "passive"))
    )
    (net (code "150") (name "unconnected-(U4-4A-Pad13)") (class "Default")
      (node (ref "U4") (pin "13") (pinfunction "4A_13") (pintype "passive"))
    )
    (net (code "151") (name "unconnected-(U4-4X-Pad11)") (class "Default")
      (node (ref "U4") (pin "11") (pinfunction "4X_11") (pintype "passive"))
    )
    (net (code "152") (name "unconnected-(U4-4Y-Pad12)") (class "Default")
      (node (ref "U4") (pin "12") (pinfunction "4Y_12") (pintype "passive"))
    )
    (net (code "153") (name "unconnected-(U5-NC-Pad4)") (class "Default")
      (node (ref "U5") (pin "4") (pinfunction "NC_4") (pintype "input"))
    )
  )
)
